# HIVE_BOARD_CHANNEL_HW.net
KiCad netlist of a schematic drawn in Altium Designer
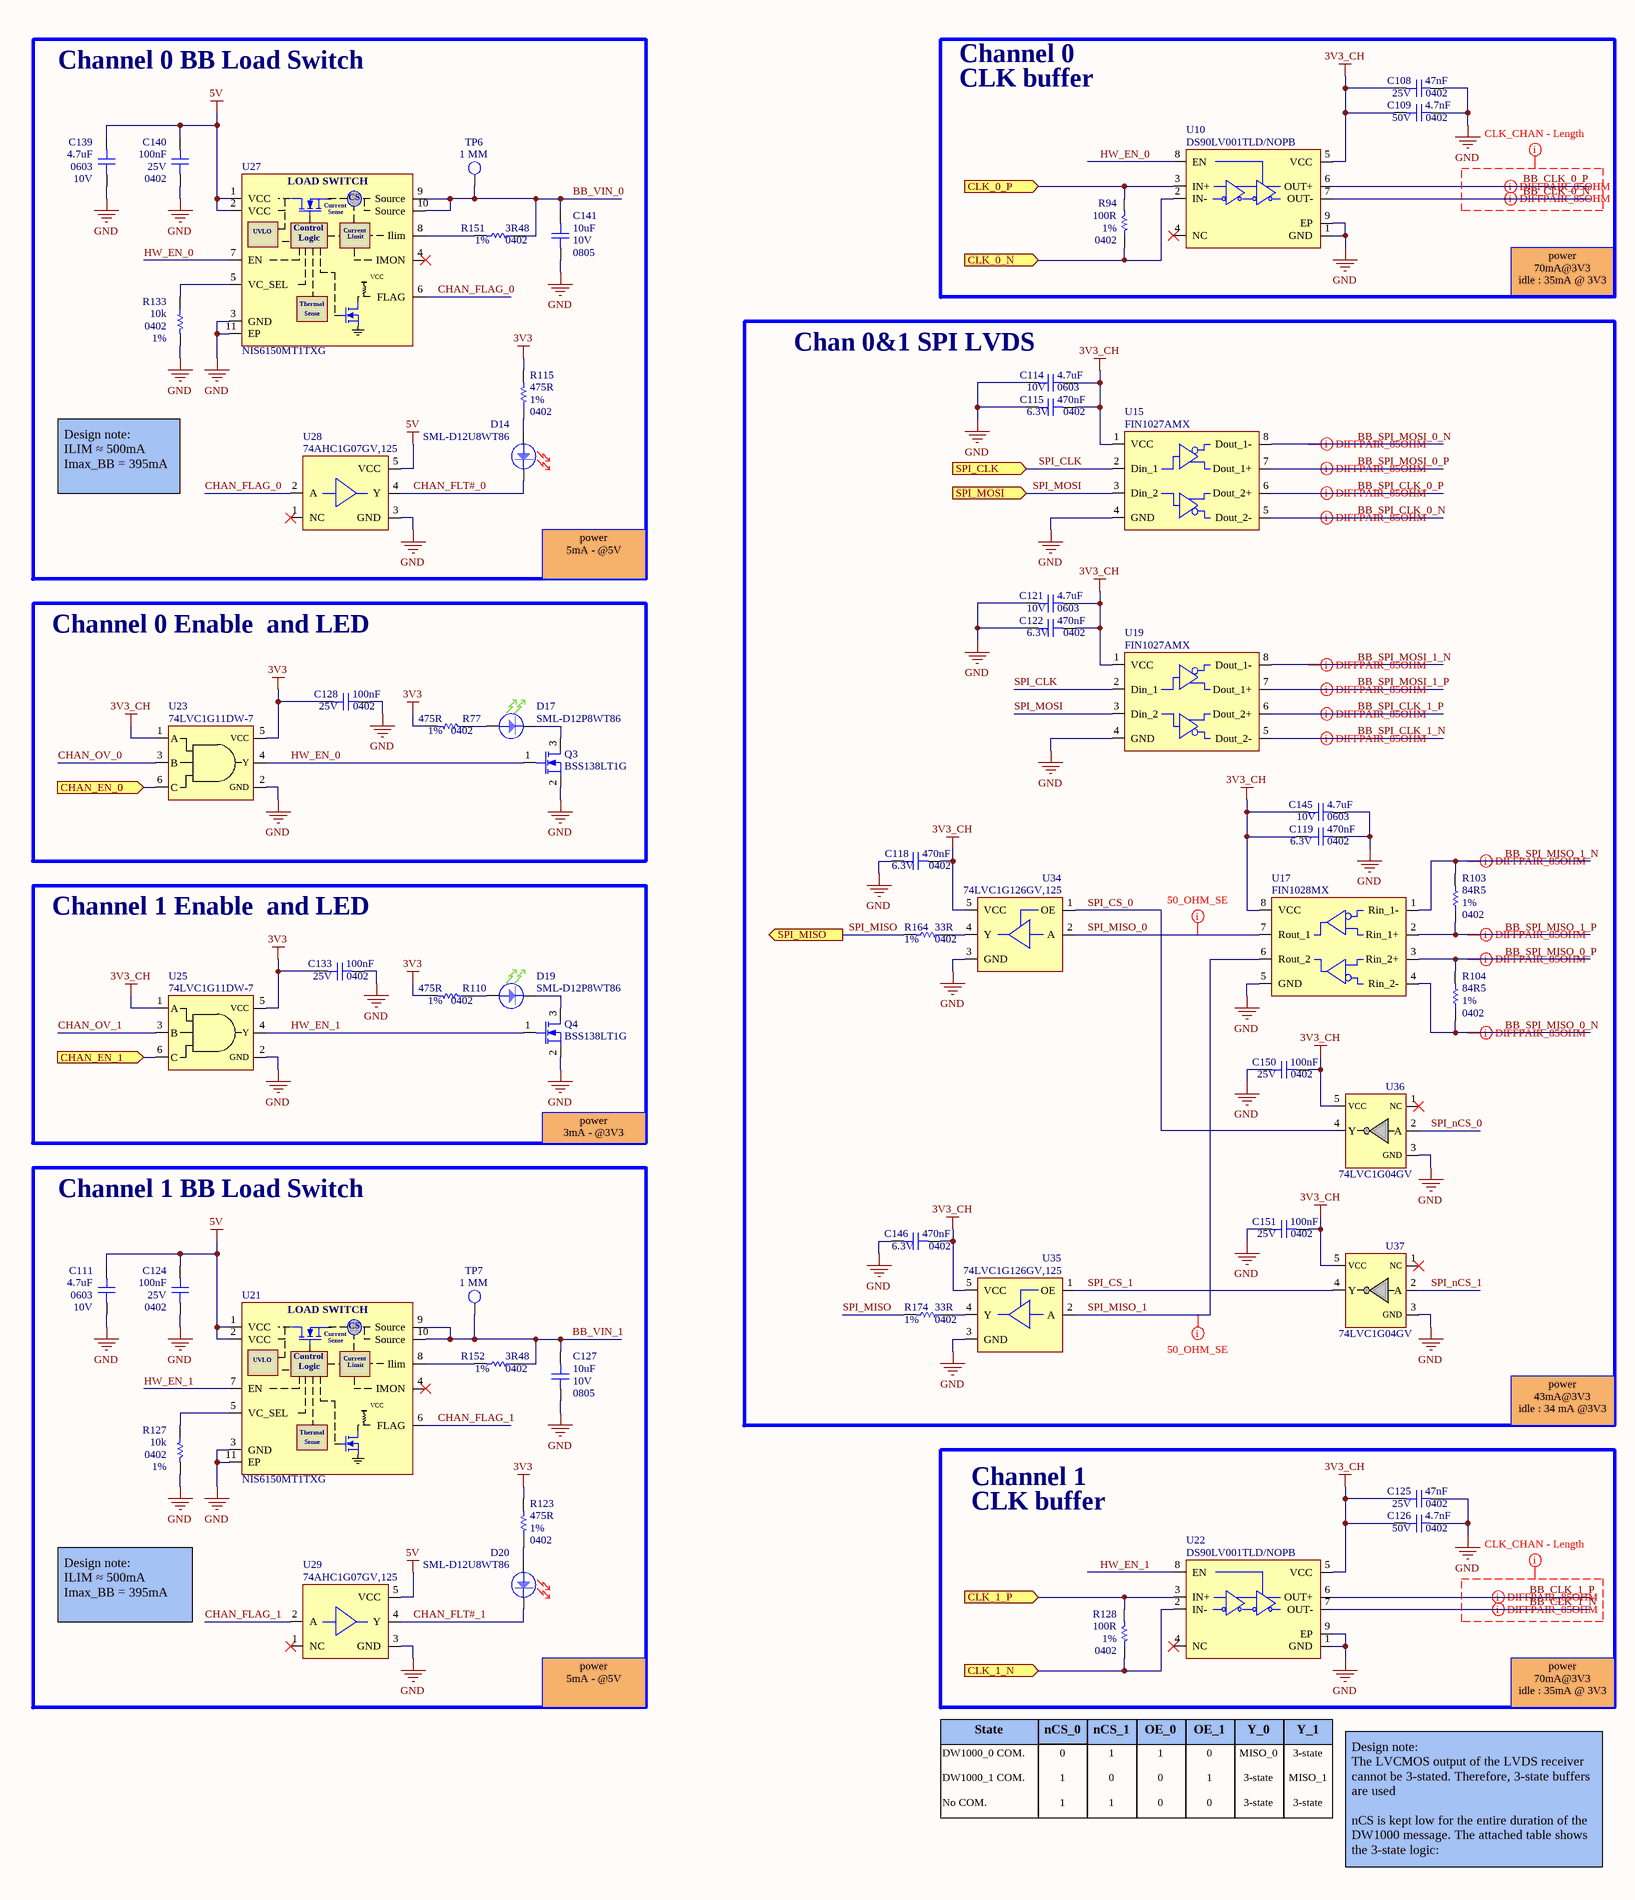
[diagram p0: HIVE_BOARD_CHANNEL_HW.SchDoc, left]
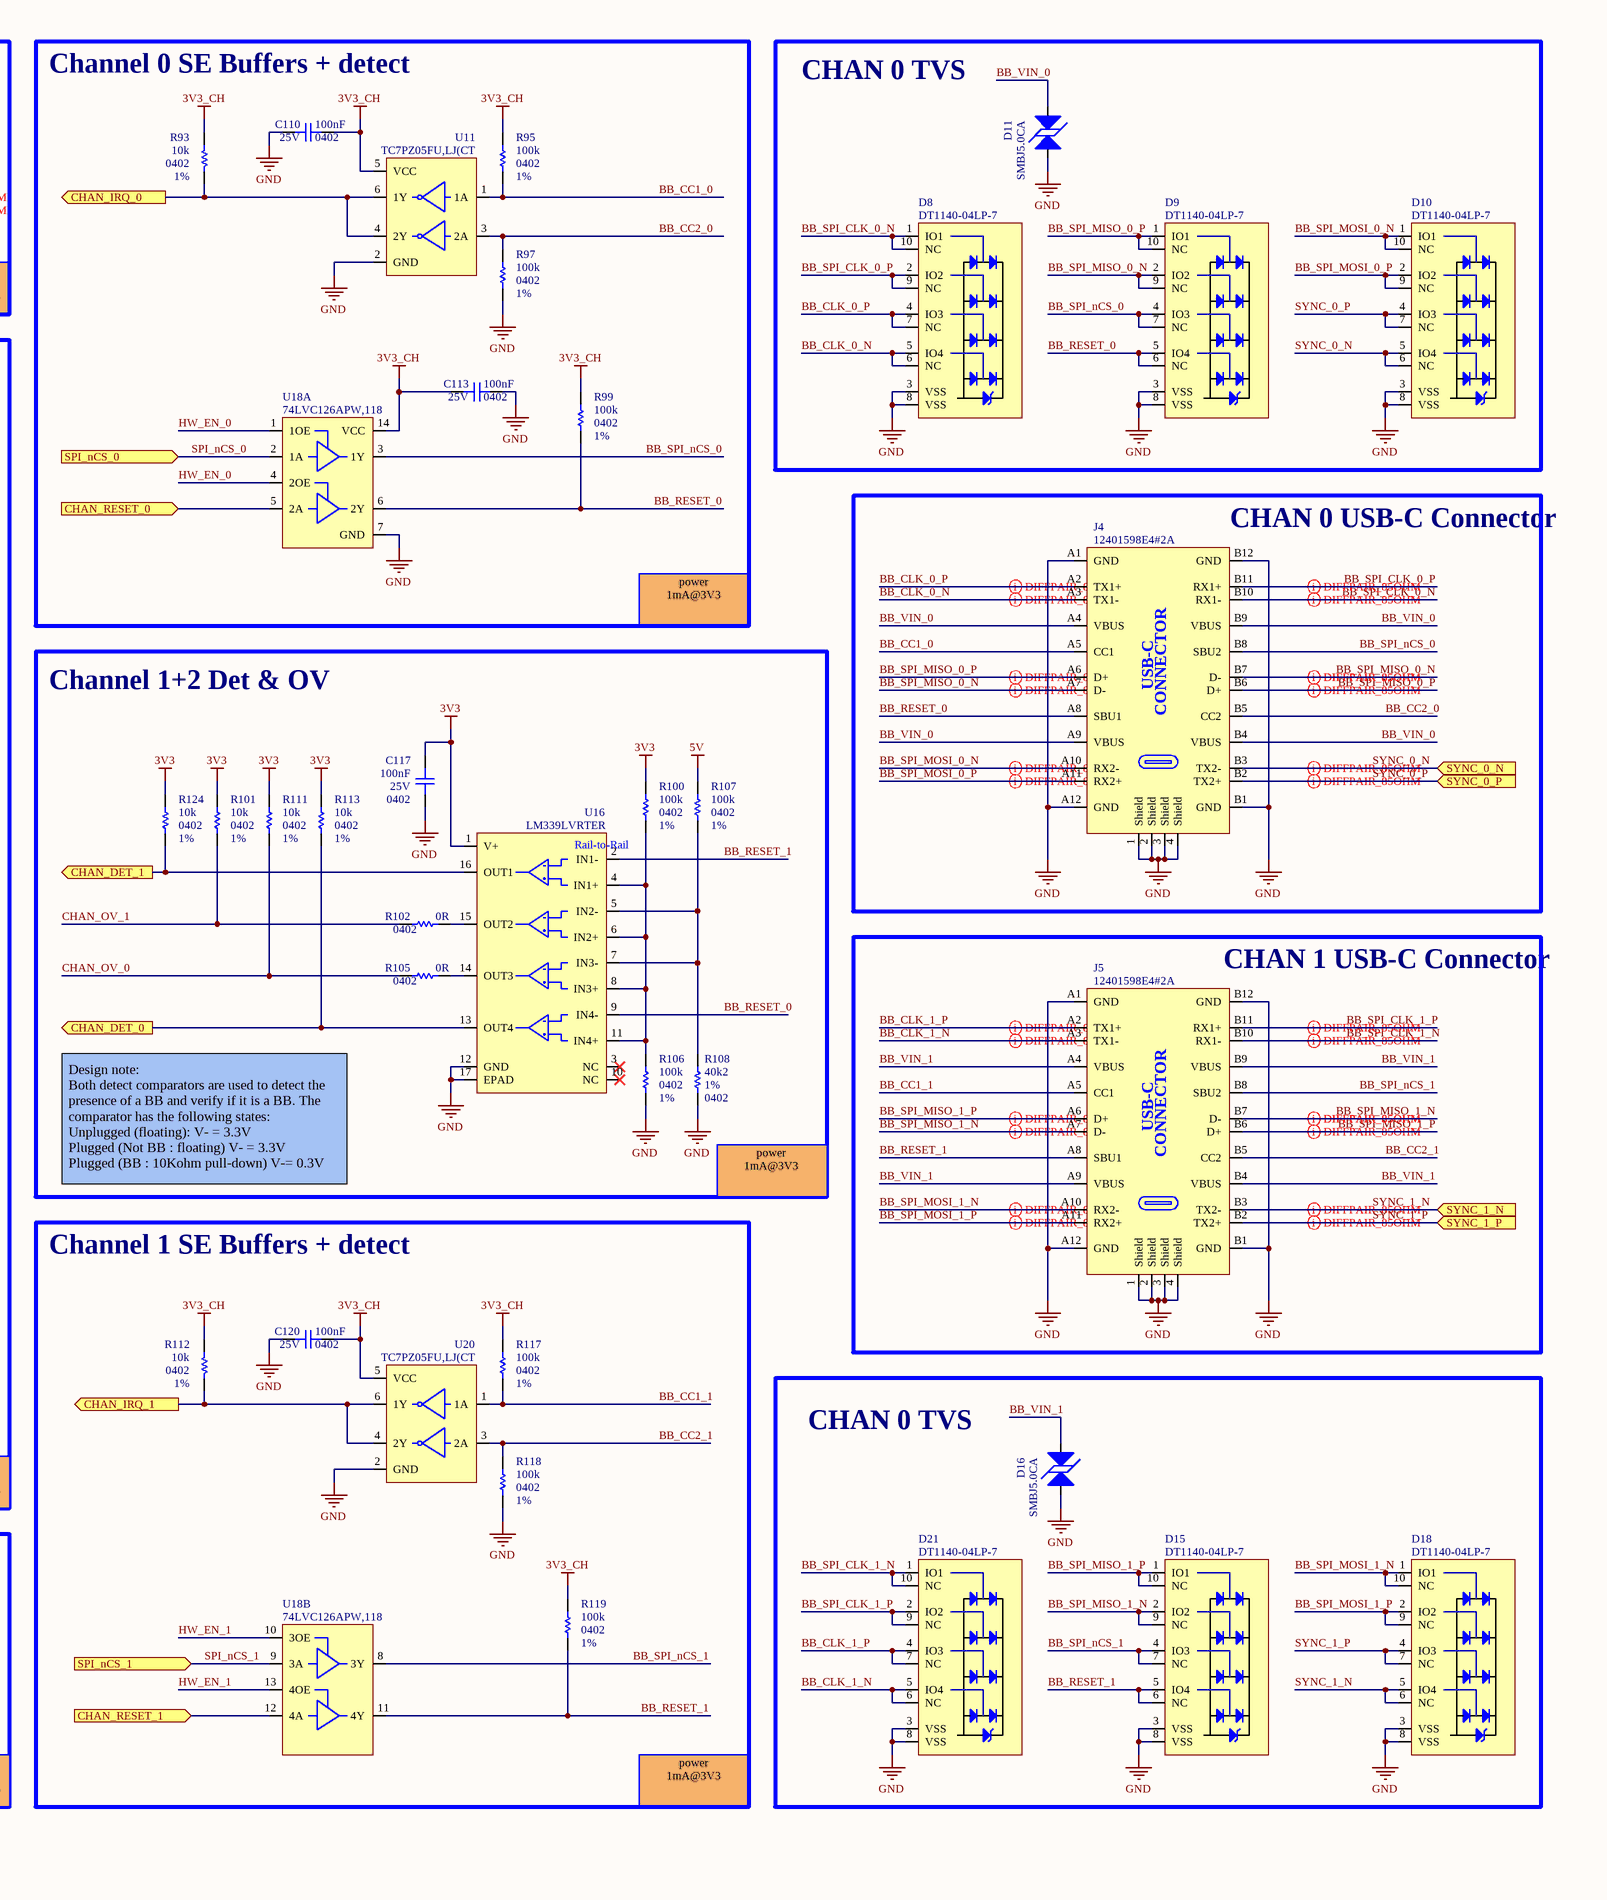
[diagram p1: HIVE_BOARD_CHANNEL_HW.SchDoc, right]

(export (version "E")
  (design (tool "Eeschema 10.0.6"))
  (components
    (comp (ref "C108")
      (value "47nF")
      (footprint "CAP_CER_0402")
      (description "CAP - CER 47nF 25V X7R - 0402")
      (fields
        (field (name "TOLERANCE") "10%")
        (field (name "PACKAGE") "0402")
        (field (name "VOLTAGE RATING") "25V")
        (field (name "Comment") "GRM155R71E473KA88J")
        (field (name "CREATEDBY/DATE") "P. Marcoux 2020-02-05")
        (field (name "VERIFIEDBY") "C.Paulin - 22/04/2020")
      )
      (libsource (lib "GRAMS_MASTER_LIB") (part "CAP_CER_GRM155R71E473KA88J"))
    )
    (comp (ref "C109")
      (value "4.7nF")
      (footprint "CAP_CER_0402")
      (description "CAP - CER 4700PF 50V X7R 0402")
      (fields
        (field (name "TOLERANCE") "±10%")
        (field (name "PACKAGE") "0402")
        (field (name "VOLTAGE RATING") "50V")
        (field (name "Comment") "CL05B472KB5VPNC")
        (field (name "CREATEDBY/DATE") "Philippe Arsenault/ 2021-03-26")
      )
      (libsource (lib "SWARMUS_LIB") (part "CAP_CER_CL05B472KB5VPNC"))
    )
    (comp (ref "C110")
      (value "100nF")
      (footprint "CAP_CER_0402")
      (description "CAP - CER 0.1µF 10% 25V X7R - 0402")
      (fields
        (field (name "TOLERANCE") "10%")
        (field (name "PACKAGE") "0402")
        (field (name "VOLTAGE RATING") "25V")
        (field (name "Comment") "CGA2B3X7R1E104K050BB")
        (field (name "CREATEDBY/DATE") "Nicolas Roy 2018-11-07")
        (field (name "VERIFIEDBY") "Nicolas V. (2019-01-22)")
      )
      (libsource (lib "GRAMS_MASTER_LIB") (part "CAP_CER_CGA2B3X7R1E104K050BB"))
    )
    (comp (ref "C111")
      (value "4.7uF")
      (footprint "CAP_CER_0603")
      (description "4.7µF ±10% 10V Ceramic Capacitor X5R 0603")
      (fields
        (field (name "TOLERANCE") "10%")
        (field (name "PACKAGE") "0603")
        (field (name "VOLTAGE RATING") "10V")
        (field (name "Comment") "CL10A475KP8NNNC")
        (field (name "CREATEDBY/DATE") "Hubert Dube - 25/02/2021")
        (field (name "VERIFIEDBY") "Philippe Arsenault/2021-03-14")
      )
      (libsource (lib "SWARMUS_LIB") (part "CAP_CER_CL10A475KP8NNNC"))
    )
    (comp (ref "C113")
      (value "100nF")
      (footprint "CAP_CER_0402")
      (description "CAP - CER 0.1µF 10% 25V X7R - 0402")
      (fields
        (field (name "TOLERANCE") "10%")
        (field (name "PACKAGE") "0402")
        (field (name "VOLTAGE RATING") "25V")
        (field (name "Comment") "CGA2B3X7R1E104K050BB")
        (field (name "CREATEDBY/DATE") "Nicolas Roy 2018-11-07")
        (field (name "VERIFIEDBY") "Nicolas V. (2019-01-22)")
      )
      (libsource (lib "GRAMS_MASTER_LIB") (part "CAP_CER_CGA2B3X7R1E104K050BB"))
    )
    (comp (ref "C114")
      (value "4.7uF")
      (footprint "CAP_CER_0603")
      (description "4.7µF ±10% 10V Ceramic Capacitor X5R 0603")
      (fields
        (field (name "TOLERANCE") "10%")
        (field (name "PACKAGE") "0603")
        (field (name "VOLTAGE RATING") "10V")
        (field (name "Comment") "CL10A475KP8NNNC")
        (field (name "CREATEDBY/DATE") "Hubert Dube - 25/02/2021")
        (field (name "VERIFIEDBY") "Philippe Arsenault/2021-03-14")
      )
      (libsource (lib "SWARMUS_LIB") (part "CAP_CER_CL10A475KP8NNNC"))
    )
    (comp (ref "C115")
      (value "470nF")
      (footprint "CAP_CER_0402")
      (description "CAP - CER 470nF 6.3V X7R - 0402")
      (fields
        (field (name "TOLERANCE") "10%")
        (field (name "PACKAGE") "0402")
        (field (name "VOLTAGE RATING") "6.3V")
        (field (name "Comment") "JMK105B7474KVHF")
        (field (name "CREATEDBY/DATE") "Nicolas (2019-06-21)")
        (field (name "VERIFIEDBY") "Nicolas V. (2019-06-21)")
      )
      (libsource (lib "GRAMS_MASTER_LIB") (part "CAP_CER_JMK105B7474KVHF"))
    )
    (comp (ref "C117")
      (value "100nF")
      (footprint "CAP_CER_0402")
      (description "CAP - CER 0.1µF 10% 25V X7R - 0402")
      (fields
        (field (name "TOLERANCE") "10%")
        (field (name "PACKAGE") "0402")
        (field (name "VOLTAGE RATING") "25V")
        (field (name "Comment") "CGA2B3X7R1E104K050BB")
        (field (name "CREATEDBY/DATE") "Nicolas Roy 2018-11-07")
        (field (name "VERIFIEDBY") "Nicolas V. (2019-01-22)")
      )
      (libsource (lib "GRAMS_MASTER_LIB") (part "CAP_CER_CGA2B3X7R1E104K050BB"))
    )
    (comp (ref "C118")
      (value "470nF")
      (footprint "CAP_CER_0402")
      (description "CAP - CER 470nF 6.3V X7R - 0402")
      (fields
        (field (name "TOLERANCE") "10%")
        (field (name "PACKAGE") "0402")
        (field (name "VOLTAGE RATING") "6.3V")
        (field (name "Comment") "JMK105B7474KVHF")
        (field (name "CREATEDBY/DATE") "Nicolas (2019-06-21)")
        (field (name "VERIFIEDBY") "Nicolas V. (2019-06-21)")
      )
      (libsource (lib "GRAMS_MASTER_LIB") (part "CAP_CER_JMK105B7474KVHF"))
    )
    (comp (ref "C119")
      (value "470nF")
      (footprint "CAP_CER_0402")
      (description "CAP - CER 470nF 6.3V X7R - 0402")
      (fields
        (field (name "TOLERANCE") "10%")
        (field (name "PACKAGE") "0402")
        (field (name "VOLTAGE RATING") "6.3V")
        (field (name "Comment") "JMK105B7474KVHF")
        (field (name "CREATEDBY/DATE") "Nicolas (2019-06-21)")
        (field (name "VERIFIEDBY") "Nicolas V. (2019-06-21)")
      )
      (libsource (lib "GRAMS_MASTER_LIB") (part "CAP_CER_JMK105B7474KVHF"))
    )
    (comp (ref "C120")
      (value "100nF")
      (footprint "CAP_CER_0402")
      (description "CAP - CER 0.1µF 10% 25V X7R - 0402")
      (fields
        (field (name "TOLERANCE") "10%")
        (field (name "PACKAGE") "0402")
        (field (name "VOLTAGE RATING") "25V")
        (field (name "Comment") "CGA2B3X7R1E104K050BB")
        (field (name "CREATEDBY/DATE") "Nicolas Roy 2018-11-07")
        (field (name "VERIFIEDBY") "Nicolas V. (2019-01-22)")
      )
      (libsource (lib "GRAMS_MASTER_LIB") (part "CAP_CER_CGA2B3X7R1E104K050BB"))
    )
    (comp (ref "C121")
      (value "4.7uF")
      (footprint "CAP_CER_0603")
      (description "4.7µF ±10% 10V Ceramic Capacitor X5R 0603")
      (fields
        (field (name "TOLERANCE") "10%")
        (field (name "PACKAGE") "0603")
        (field (name "VOLTAGE RATING") "10V")
        (field (name "Comment") "CL10A475KP8NNNC")
        (field (name "CREATEDBY/DATE") "Hubert Dube - 25/02/2021")
        (field (name "VERIFIEDBY") "Philippe Arsenault/2021-03-14")
      )
      (libsource (lib "SWARMUS_LIB") (part "CAP_CER_CL10A475KP8NNNC"))
    )
    (comp (ref "C122")
      (value "470nF")
      (footprint "CAP_CER_0402")
      (description "CAP - CER 470nF 6.3V X7R - 0402")
      (fields
        (field (name "TOLERANCE") "10%")
        (field (name "PACKAGE") "0402")
        (field (name "VOLTAGE RATING") "6.3V")
        (field (name "Comment") "JMK105B7474KVHF")
        (field (name "CREATEDBY/DATE") "Nicolas (2019-06-21)")
        (field (name "VERIFIEDBY") "Nicolas V. (2019-06-21)")
      )
      (libsource (lib "GRAMS_MASTER_LIB") (part "CAP_CER_JMK105B7474KVHF"))
    )
    (comp (ref "C124")
      (value "100nF")
      (footprint "CAP_CER_0402")
      (description "CAP - CER 0.1µF 10% 25V X7R - 0402")
      (fields
        (field (name "TOLERANCE") "10%")
        (field (name "PACKAGE") "0402")
        (field (name "VOLTAGE RATING") "25V")
        (field (name "Comment") "CGA2B3X7R1E104K050BB")
        (field (name "CREATEDBY/DATE") "Nicolas Roy 2018-11-07")
        (field (name "VERIFIEDBY") "Nicolas V. (2019-01-22)")
      )
      (libsource (lib "GRAMS_MASTER_LIB") (part "CAP_CER_CGA2B3X7R1E104K050BB"))
    )
    (comp (ref "C125")
      (value "47nF")
      (footprint "CAP_CER_0402")
      (description "CAP - CER 47nF 25V X7R - 0402")
      (fields
        (field (name "TOLERANCE") "10%")
        (field (name "PACKAGE") "0402")
        (field (name "VOLTAGE RATING") "25V")
        (field (name "Comment") "GRM155R71E473KA88J")
        (field (name "CREATEDBY/DATE") "P. Marcoux 2020-02-05")
        (field (name "VERIFIEDBY") "C.Paulin - 22/04/2020")
      )
      (libsource (lib "GRAMS_MASTER_LIB") (part "CAP_CER_GRM155R71E473KA88J"))
    )
    (comp (ref "C126")
      (value "4.7nF")
      (footprint "CAP_CER_0402")
      (description "CAP - CER 4700PF 50V X7R 0402")
      (fields
        (field (name "TOLERANCE") "±10%")
        (field (name "PACKAGE") "0402")
        (field (name "VOLTAGE RATING") "50V")
        (field (name "Comment") "CL05B472KB5VPNC")
        (field (name "CREATEDBY/DATE") "Philippe Arsenault/ 2021-03-26")
      )
      (libsource (lib "SWARMUS_LIB") (part "CAP_CER_CL05B472KB5VPNC"))
    )
    (comp (ref "C127")
      (value "10uF")
      (footprint "CAP_CER_0805")
      (description "CAP - CER 10UF 10% 10V X5R - 0805")
      (fields
        (field (name "TOLERANCE") "10%")
        (field (name "PACKAGE") "0805")
        (field (name "VOLTAGE RATING") "10V")
        (field (name "Comment") "LMK212BJ106KG-T")
        (field (name "CREATEDBY/DATE") "Caroline Paulin / 25 juillet 2018")
        (field (name "VERIFIEDBY") "Nicolas V. (2019-01-22)")
      )
      (libsource (lib "GRAMS_MASTER_LIB") (part "CAP_CER_LMK212BJ106KG-T"))
    )
    (comp (ref "C128")
      (value "100nF")
      (footprint "CAP_CER_0402")
      (description "CAP - CER 0.1µF 10% 25V X7R - 0402")
      (fields
        (field (name "TOLERANCE") "10%")
        (field (name "PACKAGE") "0402")
        (field (name "VOLTAGE RATING") "25V")
        (field (name "Comment") "CGA2B3X7R1E104K050BB")
        (field (name "CREATEDBY/DATE") "Nicolas Roy 2018-11-07")
        (field (name "VERIFIEDBY") "Nicolas V. (2019-01-22)")
      )
      (libsource (lib "GRAMS_MASTER_LIB") (part "CAP_CER_CGA2B3X7R1E104K050BB"))
    )
    (comp (ref "C133")
      (value "100nF")
      (footprint "CAP_CER_0402")
      (description "CAP - CER 0.1µF 10% 25V X7R - 0402")
      (fields
        (field (name "TOLERANCE") "10%")
        (field (name "PACKAGE") "0402")
        (field (name "VOLTAGE RATING") "25V")
        (field (name "Comment") "CGA2B3X7R1E104K050BB")
        (field (name "CREATEDBY/DATE") "Nicolas Roy 2018-11-07")
        (field (name "VERIFIEDBY") "Nicolas V. (2019-01-22)")
      )
      (libsource (lib "GRAMS_MASTER_LIB") (part "CAP_CER_CGA2B3X7R1E104K050BB"))
    )
    (comp (ref "C139")
      (value "4.7uF")
      (footprint "CAP_CER_0603")
      (description "4.7µF ±10% 10V Ceramic Capacitor X5R 0603")
      (fields
        (field (name "TOLERANCE") "10%")
        (field (name "PACKAGE") "0603")
        (field (name "VOLTAGE RATING") "10V")
        (field (name "Comment") "CL10A475KP8NNNC")
        (field (name "CREATEDBY/DATE") "Hubert Dube - 25/02/2021")
        (field (name "VERIFIEDBY") "Philippe Arsenault/2021-03-14")
      )
      (libsource (lib "SWARMUS_LIB") (part "CAP_CER_CL10A475KP8NNNC"))
    )
    (comp (ref "C140")
      (value "100nF")
      (footprint "CAP_CER_0402")
      (description "CAP - CER 0.1µF 10% 25V X7R - 0402")
      (fields
        (field (name "TOLERANCE") "10%")
        (field (name "PACKAGE") "0402")
        (field (name "VOLTAGE RATING") "25V")
        (field (name "Comment") "CGA2B3X7R1E104K050BB")
        (field (name "CREATEDBY/DATE") "Nicolas Roy 2018-11-07")
        (field (name "VERIFIEDBY") "Nicolas V. (2019-01-22)")
      )
      (libsource (lib "GRAMS_MASTER_LIB") (part "CAP_CER_CGA2B3X7R1E104K050BB"))
    )
    (comp (ref "C141")
      (value "10uF")
      (footprint "CAP_CER_0805")
      (description "CAP - CER 10UF 10% 10V X5R - 0805")
      (fields
        (field (name "TOLERANCE") "10%")
        (field (name "PACKAGE") "0805")
        (field (name "VOLTAGE RATING") "10V")
        (field (name "Comment") "LMK212BJ106KG-T")
        (field (name "CREATEDBY/DATE") "Caroline Paulin / 25 juillet 2018")
        (field (name "VERIFIEDBY") "Nicolas V. (2019-01-22)")
      )
      (libsource (lib "GRAMS_MASTER_LIB") (part "CAP_CER_LMK212BJ106KG-T"))
    )
    (comp (ref "C145")
      (value "4.7uF")
      (footprint "CAP_CER_0603")
      (description "4.7µF ±10% 10V Ceramic Capacitor X5R 0603")
      (fields
        (field (name "TOLERANCE") "10%")
        (field (name "PACKAGE") "0603")
        (field (name "VOLTAGE RATING") "10V")
        (field (name "Comment") "CL10A475KP8NNNC")
        (field (name "CREATEDBY/DATE") "Hubert Dube - 25/02/2021")
        (field (name "VERIFIEDBY") "Philippe Arsenault/2021-03-14")
      )
      (libsource (lib "SWARMUS_LIB") (part "CAP_CER_CL10A475KP8NNNC"))
    )
    (comp (ref "C146")
      (value "470nF")
      (footprint "CAP_CER_0402")
      (description "CAP - CER 470nF 6.3V X7R - 0402")
      (fields
        (field (name "TOLERANCE") "10%")
        (field (name "PACKAGE") "0402")
        (field (name "VOLTAGE RATING") "6.3V")
        (field (name "Comment") "JMK105B7474KVHF")
        (field (name "CREATEDBY/DATE") "Nicolas (2019-06-21)")
        (field (name "VERIFIEDBY") "Nicolas V. (2019-06-21)")
      )
      (libsource (lib "GRAMS_MASTER_LIB") (part "CAP_CER_JMK105B7474KVHF"))
    )
    (comp (ref "C150")
      (value "100nF")
      (footprint "CAP_CER_0402")
      (description "CAP - CER 0.1µF 10% 25V X7R - 0402")
      (fields
        (field (name "TOLERANCE") "10%")
        (field (name "PACKAGE") "0402")
        (field (name "VOLTAGE RATING") "25V")
        (field (name "Comment") "CGA2B3X7R1E104K050BB")
        (field (name "CREATEDBY/DATE") "Nicolas Roy 2018-11-07")
        (field (name "VERIFIEDBY") "Nicolas V. (2019-01-22)")
      )
      (libsource (lib "GRAMS_MASTER_LIB") (part "CAP_CER_CGA2B3X7R1E104K050BB"))
    )
    (comp (ref "C151")
      (value "100nF")
      (footprint "CAP_CER_0402")
      (description "CAP - CER 0.1µF 10% 25V X7R - 0402")
      (fields
        (field (name "TOLERANCE") "10%")
        (field (name "PACKAGE") "0402")
        (field (name "VOLTAGE RATING") "25V")
        (field (name "Comment") "CGA2B3X7R1E104K050BB")
        (field (name "CREATEDBY/DATE") "Nicolas Roy 2018-11-07")
        (field (name "VERIFIEDBY") "Nicolas V. (2019-01-22)")
      )
      (libsource (lib "GRAMS_MASTER_LIB") (part "CAP_CER_CGA2B3X7R1E104K050BB"))
    )
    (comp (ref "D8")
      (value "DT1140-04LP-7")
      (footprint "TVS_DATA_DT1140-04LP-7")
      (description "TVS - DIODE 5.5V 10V - 10-UFDFN")
      (fields
        (field (name "CREATEDBY/DATE") "Joël Lemay 2019-11-20")
        (field (name "VERIFIEDBY") "C.Paulin - 21/11/2019")
      )
      (libsource (lib "GRAMS_MASTER_LIB") (part "TVS_DATA_DT1140-04LP-7"))
    )
    (comp (ref "D9")
      (value "DT1140-04LP-7")
      (footprint "TVS_DATA_DT1140-04LP-7")
      (description "TVS - DIODE 5.5V 10V - 10-UFDFN")
      (fields
        (field (name "CREATEDBY/DATE") "Joël Lemay 2019-11-20")
        (field (name "VERIFIEDBY") "C.Paulin - 21/11/2019")
      )
      (libsource (lib "GRAMS_MASTER_LIB") (part "TVS_DATA_DT1140-04LP-7"))
    )
    (comp (ref "D10")
      (value "DT1140-04LP-7")
      (footprint "TVS_DATA_DT1140-04LP-7")
      (description "TVS - DIODE 5.5V 10V - 10-UFDFN")
      (fields
        (field (name "CREATEDBY/DATE") "Joël Lemay 2019-11-20")
        (field (name "VERIFIEDBY") "C.Paulin - 21/11/2019")
      )
      (libsource (lib "GRAMS_MASTER_LIB") (part "TVS_DATA_DT1140-04LP-7"))
    )
    (comp (ref "D11")
      (value "SMBJ5.0CA")
      (footprint "TVS_PWR_SMBJ5.0CA")
      (description "TVS - BIDIR 5V 9.2V 600W - DO214AA")
      (fields
        (field (name "CREATEDBY/DATE") "Jonathan Bouchard - 2019-03-22")
        (field (name "VERIFIEDBY") "Nicolas V. (2019-05-06)")
      )
      (libsource (lib "GRAMS_MASTER_LIB") (part "TVS_PWR_SMBJ5.0CA"))
    )
    (comp (ref "D14")
      (value "SML-D12U8WT86")
      (footprint "LED_SML-D12U8WT86")
      (description "LED - RED DIFFUSED 0603 SMD - 0603")
      (fields
        (field (name "CREATEDBY/DATE") "Olivier Bernard / 01/02/2018")
        (field (name "VERIFIEDBY") "Caroline Paulin / 6 juillet 2018")
      )
      (libsource (lib "GRAMS_MASTER_LIB") (part "LED_SML-D12U8WT86"))
    )
    (comp (ref "D15")
      (value "DT1140-04LP-7")
      (footprint "TVS_DATA_DT1140-04LP-7")
      (description "TVS - DIODE 5.5V 10V - 10-UFDFN")
      (fields
        (field (name "CREATEDBY/DATE") "Joël Lemay 2019-11-20")
        (field (name "VERIFIEDBY") "C.Paulin - 21/11/2019")
      )
      (libsource (lib "GRAMS_MASTER_LIB") (part "TVS_DATA_DT1140-04LP-7"))
    )
    (comp (ref "D16")
      (value "SMBJ5.0CA")
      (footprint "TVS_PWR_SMBJ5.0CA")
      (description "TVS - BIDIR 5V 9.2V 600W - DO214AA")
      (fields
        (field (name "CREATEDBY/DATE") "Jonathan Bouchard - 2019-03-22")
        (field (name "VERIFIEDBY") "Nicolas V. (2019-05-06)")
      )
      (libsource (lib "GRAMS_MASTER_LIB") (part "TVS_PWR_SMBJ5.0CA"))
    )
    (comp (ref "D17")
      (value "SML-D12P8WT86")
      (footprint "LED_SML-D12P8WT86")
      (description "LED - GREEN DIFFUSED 0603 SMD - 0603")
      (fields
        (field (name "CREATEDBY/DATE") "Keven Deslandes - 2018/11/21")
        (field (name "VERIFIEDBY") "Caroline Paulin - 13 février 2019")
      )
      (libsource (lib "GRAMS_MASTER_LIB") (part "LED_SML-D12P8WT86"))
    )
    (comp (ref "D18")
      (value "DT1140-04LP-7")
      (footprint "TVS_DATA_DT1140-04LP-7")
      (description "TVS - DIODE 5.5V 10V - 10-UFDFN")
      (fields
        (field (name "CREATEDBY/DATE") "Joël Lemay 2019-11-20")
        (field (name "VERIFIEDBY") "C.Paulin - 21/11/2019")
      )
      (libsource (lib "GRAMS_MASTER_LIB") (part "TVS_DATA_DT1140-04LP-7"))
    )
    (comp (ref "D19")
      (value "SML-D12P8WT86")
      (footprint "LED_SML-D12P8WT86")
      (description "LED - GREEN DIFFUSED 0603 SMD - 0603")
      (fields
        (field (name "CREATEDBY/DATE") "Keven Deslandes - 2018/11/21")
        (field (name "VERIFIEDBY") "Caroline Paulin - 13 février 2019")
      )
      (libsource (lib "GRAMS_MASTER_LIB") (part "LED_SML-D12P8WT86"))
    )
    (comp (ref "D20")
      (value "SML-D12U8WT86")
      (footprint "LED_SML-D12U8WT86")
      (description "LED - RED DIFFUSED 0603 SMD - 0603")
      (fields
        (field (name "CREATEDBY/DATE") "Olivier Bernard / 01/02/2018")
        (field (name "VERIFIEDBY") "Caroline Paulin / 6 juillet 2018")
      )
      (libsource (lib "GRAMS_MASTER_LIB") (part "LED_SML-D12U8WT86"))
    )
    (comp (ref "D21")
      (value "DT1140-04LP-7")
      (footprint "TVS_DATA_DT1140-04LP-7")
      (description "TVS - DIODE 5.5V 10V - 10-UFDFN")
      (fields
        (field (name "CREATEDBY/DATE") "Joël Lemay 2019-11-20")
        (field (name "VERIFIEDBY") "C.Paulin - 21/11/2019")
      )
      (libsource (lib "GRAMS_MASTER_LIB") (part "TVS_DATA_DT1140-04LP-7"))
    )
    (comp (ref "J4")
      (value "12401598E4#2A")
      (footprint "CON_USB_3.2_TypeC_12401598E4#2A")
      (description "CON_USB - USB 3.2 Gen 2 (USB 3.1 Gen 2, Superspeed + (USB 3.1)) 24 pos Receptacle - R/A")
      (fields
        (field (name "CREATEDBY/DATE") "Louis-Daniel Gaulin / 07-04-2021")
        (field (name "VERIFIEDBY") "Philippe Arsenault/2021-04-08")
      )
      (libsource (lib "SWARMUS_LIB") (part "CON_USB_3.2_TypeC_12401598E4#2A"))
    )
    (comp (ref "J5")
      (value "12401598E4#2A")
      (footprint "CON_USB_3.2_TypeC_12401598E4#2A")
      (description "CON_USB - USB 3.2 Gen 2 (USB 3.1 Gen 2, Superspeed + (USB 3.1)) 24 pos Receptacle - R/A")
      (fields
        (field (name "CREATEDBY/DATE") "Louis-Daniel Gaulin / 07-04-2021")
        (field (name "VERIFIEDBY") "Philippe Arsenault/2021-04-08")
      )
      (libsource (lib "SWARMUS_LIB") (part "CON_USB_3.2_TypeC_12401598E4#2A"))
    )
    (comp (ref "Q3")
      (value "BSS138LT1G")
      (footprint "TRX_NMOS_BSS138LT1G")
      (description "TRX - NMOS - 50V 200MA - SOT−23-3")
      (fields
        (field (name "CREATEDBY/DATE") "Joel Lemay 2018-06-15")
        (field (name "VERIFIEDBY") "Caroline Paulin - 6 sept 2018")
      )
      (libsource (lib "GRAMS_MASTER_LIB") (part "TRX_NMOS_BSS138LT1G"))
    )
    (comp (ref "Q4")
      (value "BSS138LT1G")
      (footprint "TRX_NMOS_BSS138LT1G")
      (description "TRX - NMOS - 50V 200MA - SOT−23-3")
      (fields
        (field (name "CREATEDBY/DATE") "Joel Lemay 2018-06-15")
        (field (name "VERIFIEDBY") "Caroline Paulin - 6 sept 2018")
      )
      (libsource (lib "GRAMS_MASTER_LIB") (part "TRX_NMOS_BSS138LT1G"))
    )
    (comp (ref "R77")
      (value "475R")
      (footprint "RES_0402")
      (description "RES - 475R 1% 1/10W- 0402")
      (fields
        (field (name "TOLERANCE") "1%")
        (field (name "PACKAGE") "0402")
        (field (name "Comment") "ERJ-2RKF4750X")
        (field (name "CREATEDBY/DATE") "Keven Deslandes 2018-10-17")
        (field (name "VERIFIEDBY") "Carolilne Paulin - 18/12/2018")
      )
      (libsource (lib "GRAMS_MASTER_LIB") (part "RES_ERJ-2RKF4750X"))
    )
    (comp (ref "R93")
      (value "10k")
      (footprint "RES_0402")
      (description "RES - 10K OHMS 1% 1/16W - 0402")
      (fields
        (field (name "TOLERANCE") "1%")
        (field (name "PACKAGE") "0402")
        (field (name "Comment") "RC0402FR-0710KL")
        (field (name "CREATEDBY/DATE") "Nicolas V. (2018-11-20)")
        (field (name "VERIFIEDBY") "Nicolas V. (2018-11-20)")
      )
      (libsource (lib "GRAMS_MASTER_LIB") (part "RES_RC0402FR-0710KL"))
    )
    (comp (ref "R94")
      (value "100R")
      (footprint "RES_0402")
      (description "RES - 100R OHM 1% 1/16W - 0402")
      (fields
        (field (name "TOLERANCE") "1%")
        (field (name "PACKAGE") "0402")
        (field (name "Comment") "RC0402FR-07100RP")
        (field (name "CREATEDBY/DATE") "Jonathan Bouchard 2018-07-05")
        (field (name "VERIFIEDBY") "Arnaud Samson 16-07-18")
      )
      (libsource (lib "GRAMS_MASTER_LIB") (part "RES_RC0402FR-07100RP"))
    )
    (comp (ref "R95")
      (value "100k")
      (footprint "RES_0402")
      (description "RES - 100K 1% 1/16W - 0402")
      (fields
        (field (name "TOLERANCE") "1%")
        (field (name "PACKAGE") "0402")
        (field (name "Comment") "RC0402FR-07100KL")
        (field (name "CREATEDBY/DATE") "Keven Deslandes 2018-10-19")
        (field (name "VERIFIEDBY") "Caroline Paulin - 18/12/2018")
      )
      (libsource (lib "GRAMS_MASTER_LIB") (part "RES_RC0402FR-07100KL"))
    )
    (comp (ref "R97")
      (value "100k")
      (footprint "RES_0402")
      (description "RES - 100K 1% 1/16W - 0402")
      (fields
        (field (name "TOLERANCE") "1%")
        (field (name "PACKAGE") "0402")
        (field (name "Comment") "RC0402FR-07100KL")
        (field (name "CREATEDBY/DATE") "Keven Deslandes 2018-10-19")
        (field (name "VERIFIEDBY") "Caroline Paulin - 18/12/2018")
      )
      (libsource (lib "GRAMS_MASTER_LIB") (part "RES_RC0402FR-07100KL"))
    )
    (comp (ref "R99")
      (value "100k")
      (footprint "RES_0402")
      (description "RES - 100K 1% 1/16W - 0402")
      (fields
        (field (name "TOLERANCE") "1%")
        (field (name "PACKAGE") "0402")
        (field (name "Comment") "RC0402FR-07100KL")
        (field (name "CREATEDBY/DATE") "Keven Deslandes 2018-10-19")
        (field (name "VERIFIEDBY") "Caroline Paulin - 18/12/2018")
      )
      (libsource (lib "GRAMS_MASTER_LIB") (part "RES_RC0402FR-07100KL"))
    )
    (comp (ref "R100")
      (value "100k")
      (footprint "RES_0402")
      (description "RES - 100K 1% 1/16W - 0402")
      (fields
        (field (name "TOLERANCE") "1%")
        (field (name "PACKAGE") "0402")
        (field (name "Comment") "RC0402FR-07100KL")
        (field (name "CREATEDBY/DATE") "Keven Deslandes 2018-10-19")
        (field (name "VERIFIEDBY") "Caroline Paulin - 18/12/2018")
      )
      (libsource (lib "GRAMS_MASTER_LIB") (part "RES_RC0402FR-07100KL"))
    )
    (comp (ref "R101")
      (value "10k")
      (footprint "RES_0402")
      (description "RES - 10K OHMS 1% 1/16W - 0402")
      (fields
        (field (name "TOLERANCE") "1%")
        (field (name "PACKAGE") "0402")
        (field (name "Comment") "RC0402FR-0710KL")
        (field (name "CREATEDBY/DATE") "Nicolas V. (2018-11-20)")
        (field (name "VERIFIEDBY") "Nicolas V. (2018-11-20)")
      )
      (libsource (lib "GRAMS_MASTER_LIB") (part "RES_RC0402FR-0710KL"))
    )
    (comp (ref "R102")
      (value "0R")
      (footprint "RES_0402")
      (description "RES - 0R 1/16W 1A  - 0402")
      (fields
        (field (name "PACKAGE") "0402")
        (field (name "Comment") "RC0402FR-070RL")
        (field (name "CREATEDBY/DATE") "Keven Deslandes 2018-09-12")
        (field (name "VERIFIEDBY") "Caroline Paulin - 27 fév 2019")
      )
      (libsource (lib "GRAMS_MASTER_LIB") (part "RES_RC0402FR-070RL"))
    )
    (comp (ref "R103")
      (value "84R5")
      (footprint "RES_0402")
      (description "RES - 84R5 1% 1/16W - 0402")
      (fields
        (field (name "TOLERANCE") "1%")
        (field (name "PACKAGE") "0402")
        (field (name "Comment") "RC0402FR-0784R5L")
        (field (name "CREATEDBY/DATE") "Philippe Arsenault/ 2021-03-31")
      )
      (libsource (lib "SWARMUS_LIB") (part "RES_RC0402FR-0784R5L"))
    )
    (comp (ref "R104")
      (value "84R5")
      (footprint "RES_0402")
      (description "RES - 84R5 1% 1/16W - 0402")
      (fields
        (field (name "TOLERANCE") "1%")
        (field (name "PACKAGE") "0402")
        (field (name "Comment") "RC0402FR-0784R5L")
        (field (name "CREATEDBY/DATE") "Philippe Arsenault/ 2021-03-31")
      )
      (libsource (lib "SWARMUS_LIB") (part "RES_RC0402FR-0784R5L"))
    )
    (comp (ref "R105")
      (value "0R")
      (footprint "RES_0402")
      (description "RES - 0R 1/16W 1A  - 0402")
      (fields
        (field (name "PACKAGE") "0402")
        (field (name "Comment") "RC0402FR-070RL")
        (field (name "CREATEDBY/DATE") "Keven Deslandes 2018-09-12")
        (field (name "VERIFIEDBY") "Caroline Paulin - 27 fév 2019")
      )
      (libsource (lib "GRAMS_MASTER_LIB") (part "RES_RC0402FR-070RL"))
    )
    (comp (ref "R106")
      (value "100k")
      (footprint "RES_0402")
      (description "RES - 100K 1% 1/16W - 0402")
      (fields
        (field (name "TOLERANCE") "1%")
        (field (name "PACKAGE") "0402")
        (field (name "Comment") "RC0402FR-07100KL")
        (field (name "CREATEDBY/DATE") "Keven Deslandes 2018-10-19")
        (field (name "VERIFIEDBY") "Caroline Paulin - 18/12/2018")
      )
      (libsource (lib "GRAMS_MASTER_LIB") (part "RES_RC0402FR-07100KL"))
    )
    (comp (ref "R107")
      (value "100k")
      (footprint "RES_0402")
      (description "RES - 100K 1% 1/16W - 0402")
      (fields
        (field (name "TOLERANCE") "1%")
        (field (name "PACKAGE") "0402")
        (field (name "Comment") "RC0402FR-07100KL")
        (field (name "CREATEDBY/DATE") "Keven Deslandes 2018-10-19")
        (field (name "VERIFIEDBY") "Caroline Paulin - 18/12/2018")
      )
      (libsource (lib "GRAMS_MASTER_LIB") (part "RES_RC0402FR-07100KL"))
    )
    (comp (ref "R108")
      (value "40k2")
      (footprint "RES_0402")
      (description "RES - 40.2K 1% 1/16W - 0402")
      (fields
        (field (name "TOLERANCE") "1%")
        (field (name "PACKAGE") "0402")
        (field (name "Comment") "RC0402FR-0740K2L")
        (field (name "CREATEDBY/DATE") "Raphael Bouchard - 2019-08-09")
        (field (name "VERIFIEDBY") "C.Paulin - 15/08/2019")
      )
      (libsource (lib "GRAMS_MASTER_LIB") (part "RES_RC0402FR-0740K2L"))
    )
    (comp (ref "R110")
      (value "475R")
      (footprint "RES_0402")
      (description "RES - 475R 1% 1/10W- 0402")
      (fields
        (field (name "TOLERANCE") "1%")
        (field (name "PACKAGE") "0402")
        (field (name "Comment") "ERJ-2RKF4750X")
        (field (name "CREATEDBY/DATE") "Keven Deslandes 2018-10-17")
        (field (name "VERIFIEDBY") "Carolilne Paulin - 18/12/2018")
      )
      (libsource (lib "GRAMS_MASTER_LIB") (part "RES_ERJ-2RKF4750X"))
    )
    (comp (ref "R111")
      (value "10k")
      (footprint "RES_0402")
      (description "RES - 10K OHMS 1% 1/16W - 0402")
      (fields
        (field (name "TOLERANCE") "1%")
        (field (name "PACKAGE") "0402")
        (field (name "Comment") "RC0402FR-0710KL")
        (field (name "CREATEDBY/DATE") "Nicolas V. (2018-11-20)")
        (field (name "VERIFIEDBY") "Nicolas V. (2018-11-20)")
      )
      (libsource (lib "GRAMS_MASTER_LIB") (part "RES_RC0402FR-0710KL"))
    )
    (comp (ref "R112")
      (value "10k")
      (footprint "RES_0402")
      (description "RES - 10K OHMS 1% 1/16W - 0402")
      (fields
        (field (name "TOLERANCE") "1%")
        (field (name "PACKAGE") "0402")
        (field (name "Comment") "RC0402FR-0710KL")
        (field (name "CREATEDBY/DATE") "Nicolas V. (2018-11-20)")
        (field (name "VERIFIEDBY") "Nicolas V. (2018-11-20)")
      )
      (libsource (lib "GRAMS_MASTER_LIB") (part "RES_RC0402FR-0710KL"))
    )
    (comp (ref "R113")
      (value "10k")
      (footprint "RES_0402")
      (description "RES - 10K OHMS 1% 1/16W - 0402")
      (fields
        (field (name "TOLERANCE") "1%")
        (field (name "PACKAGE") "0402")
        (field (name "Comment") "RC0402FR-0710KL")
        (field (name "CREATEDBY/DATE") "Nicolas V. (2018-11-20)")
        (field (name "VERIFIEDBY") "Nicolas V. (2018-11-20)")
      )
      (libsource (lib "GRAMS_MASTER_LIB") (part "RES_RC0402FR-0710KL"))
    )
    (comp (ref "R115")
      (value "475R")
      (footprint "RES_0402")
      (description "RES - 475R 1% 1/10W- 0402")
      (fields
        (field (name "TOLERANCE") "1%")
        (field (name "PACKAGE") "0402")
        (field (name "Comment") "ERJ-2RKF4750X")
        (field (name "CREATEDBY/DATE") "Keven Deslandes 2018-10-17")
        (field (name "VERIFIEDBY") "Carolilne Paulin - 18/12/2018")
      )
      (libsource (lib "GRAMS_MASTER_LIB") (part "RES_ERJ-2RKF4750X"))
    )
    (comp (ref "R117")
      (value "100k")
      (footprint "RES_0402")
      (description "RES - 100K 1% 1/16W - 0402")
      (fields
        (field (name "TOLERANCE") "1%")
        (field (name "PACKAGE") "0402")
        (field (name "Comment") "RC0402FR-07100KL")
        (field (name "CREATEDBY/DATE") "Keven Deslandes 2018-10-19")
        (field (name "VERIFIEDBY") "Caroline Paulin - 18/12/2018")
      )
      (libsource (lib "GRAMS_MASTER_LIB") (part "RES_RC0402FR-07100KL"))
    )
    (comp (ref "R118")
      (value "100k")
      (footprint "RES_0402")
      (description "RES - 100K 1% 1/16W - 0402")
      (fields
        (field (name "TOLERANCE") "1%")
        (field (name "PACKAGE") "0402")
        (field (name "Comment") "RC0402FR-07100KL")
        (field (name "CREATEDBY/DATE") "Keven Deslandes 2018-10-19")
        (field (name "VERIFIEDBY") "Caroline Paulin - 18/12/2018")
      )
      (libsource (lib "GRAMS_MASTER_LIB") (part "RES_RC0402FR-07100KL"))
    )
    (comp (ref "R119")
      (value "100k")
      (footprint "RES_0402")
      (description "RES - 100K 1% 1/16W - 0402")
      (fields
        (field (name "TOLERANCE") "1%")
        (field (name "PACKAGE") "0402")
        (field (name "Comment") "RC0402FR-07100KL")
        (field (name "CREATEDBY/DATE") "Keven Deslandes 2018-10-19")
        (field (name "VERIFIEDBY") "Caroline Paulin - 18/12/2018")
      )
      (libsource (lib "GRAMS_MASTER_LIB") (part "RES_RC0402FR-07100KL"))
    )
    (comp (ref "R123")
      (value "475R")
      (footprint "RES_0402")
      (description "RES - 475R 1% 1/10W- 0402")
      (fields
        (field (name "TOLERANCE") "1%")
        (field (name "PACKAGE") "0402")
        (field (name "Comment") "ERJ-2RKF4750X")
        (field (name "CREATEDBY/DATE") "Keven Deslandes 2018-10-17")
        (field (name "VERIFIEDBY") "Carolilne Paulin - 18/12/2018")
      )
      (libsource (lib "GRAMS_MASTER_LIB") (part "RES_ERJ-2RKF4750X"))
    )
    (comp (ref "R124")
      (value "10k")
      (footprint "RES_0402")
      (description "RES - 10K OHMS 1% 1/16W - 0402")
      (fields
        (field (name "TOLERANCE") "1%")
        (field (name "PACKAGE") "0402")
        (field (name "Comment") "RC0402FR-0710KL")
        (field (name "CREATEDBY/DATE") "Nicolas V. (2018-11-20)")
        (field (name "VERIFIEDBY") "Nicolas V. (2018-11-20)")
      )
      (libsource (lib "GRAMS_MASTER_LIB") (part "RES_RC0402FR-0710KL"))
    )
    (comp (ref "R127")
      (value "10k")
      (footprint "RES_0402")
      (description "RES - 10K OHMS 1% 1/16W - 0402")
      (fields
        (field (name "TOLERANCE") "1%")
        (field (name "PACKAGE") "0402")
        (field (name "Comment") "RC0402FR-0710KL")
        (field (name "CREATEDBY/DATE") "Nicolas V. (2018-11-20)")
        (field (name "VERIFIEDBY") "Nicolas V. (2018-11-20)")
      )
      (libsource (lib "GRAMS_MASTER_LIB") (part "RES_RC0402FR-0710KL"))
    )
    (comp (ref "R128")
      (value "100R")
      (footprint "RES_0402")
      (description "RES - 100R OHM 1% 1/16W - 0402")
      (fields
        (field (name "TOLERANCE") "1%")
        (field (name "PACKAGE") "0402")
        (field (name "Comment") "RC0402FR-07100RP")
        (field (name "CREATEDBY/DATE") "Jonathan Bouchard 2018-07-05")
        (field (name "VERIFIEDBY") "Arnaud Samson 16-07-18")
      )
      (libsource (lib "GRAMS_MASTER_LIB") (part "RES_RC0402FR-07100RP"))
    )
    (comp (ref "R133")
      (value "10k")
      (footprint "RES_0402")
      (description "RES - 10K OHMS 1% 1/16W - 0402")
      (fields
        (field (name "TOLERANCE") "1%")
        (field (name "PACKAGE") "0402")
        (field (name "Comment") "RC0402FR-0710KL")
        (field (name "CREATEDBY/DATE") "Nicolas V. (2018-11-20)")
        (field (name "VERIFIEDBY") "Nicolas V. (2018-11-20)")
      )
      (libsource (lib "GRAMS_MASTER_LIB") (part "RES_RC0402FR-0710KL"))
    )
    (comp (ref "R151")
      (value "3R48")
      (footprint "RES_0402")
      (description "RES - 3.48 R ±1% 1/16W -  0402")
      (fields
        (field (name "TOLERANCE") "1%")
        (field (name "PACKAGE") "0402")
        (field (name "Comment") "CRCW04023R48FKED")
        (field (name "CREATEDBY/DATE") "Louis-Daniel Gaulin / 2021-05-01")
        (field (name "VERIFIEDBY") "Philippe Arsenault/2021-05-10")
      )
      (libsource (lib "SWARMUS_LIB") (part "RES_CRCW04023R48FKED"))
    )
    (comp (ref "R152")
      (value "3R48")
      (footprint "RES_0402")
      (description "RES - 3.48 R ±1% 1/16W -  0402")
      (fields
        (field (name "TOLERANCE") "1%")
        (field (name "PACKAGE") "0402")
        (field (name "Comment") "CRCW04023R48FKED")
        (field (name "CREATEDBY/DATE") "Louis-Daniel Gaulin / 2021-05-01")
        (field (name "VERIFIEDBY") "Philippe Arsenault/2021-05-10")
      )
      (libsource (lib "SWARMUS_LIB") (part "RES_CRCW04023R48FKED"))
    )
    (comp (ref "R164")
      (value "33R")
      (footprint "RES_0402")
      (description "RES - 33 OHM 1% 1/16W - 0402")
      (fields
        (field (name "TOLERANCE") "1%")
        (field (name "PACKAGE") "0402")
        (field (name "Comment") "RC0402FR-0733RL")
        (field (name "CREATEDBY/DATE") "Louis-Daniel Gaulin/ 14/01/2020")
        (field (name "VERIFIEDBY") "C.Paulin - 21/01/2020")
      )
      (libsource (lib "GRAMS_MASTER_LIB") (part "RES_RC0402FR-0733RL"))
    )
    (comp (ref "R174")
      (value "33R")
      (footprint "RES_0402")
      (description "RES - 33 OHM 1% 1/16W - 0402")
      (fields
        (field (name "TOLERANCE") "1%")
        (field (name "PACKAGE") "0402")
        (field (name "Comment") "RC0402FR-0733RL")
        (field (name "CREATEDBY/DATE") "Louis-Daniel Gaulin/ 14/01/2020")
        (field (name "VERIFIEDBY") "C.Paulin - 21/01/2020")
      )
      (libsource (lib "GRAMS_MASTER_LIB") (part "RES_RC0402FR-0733RL"))
    )
    (comp (ref "TP6")
      (value "1 MM")
      (footprint "TPO_SMD_ROUND_1MM")
      (description "TPO - TEST POINT ROUND SMD PAD ONLY  - 1 MM")
      (fields
        (field (name "CREATEDBY/DATE") "Jonathan Bouchard 2018-07-17")
        (field (name "VERIFIEDBY") "Arnaud Samson 23-07-18")
      )
      (libsource (lib "GRAMS_MASTER_LIB") (part "TPO_SMD_ROUND_1MM"))
    )
    (comp (ref "TP7")
      (value "1 MM")
      (footprint "TPO_SMD_ROUND_1MM")
      (description "TPO - TEST POINT ROUND SMD PAD ONLY  - 1 MM")
      (fields
        (field (name "CREATEDBY/DATE") "Jonathan Bouchard 2018-07-17")
        (field (name "VERIFIEDBY") "Arnaud Samson 23-07-18")
      )
      (libsource (lib "GRAMS_MASTER_LIB") (part "TPO_SMD_ROUND_1MM"))
    )
    (comp (ref "U10")
      (value "DS90LV001TLD/NOPB")
      (footprint "COM_BUF_DS90LV001TLD/NOPB")
      (description "COM_BUF - ReDriver 1 Channel 800Mbps CML,LVDS,LVPECL to LVDS -  \r\n8-WFDFN EP")
      (fields
        (field (name "CREATEDBY/DATE") "Louis-Daniel Gaulin / 07-04-2021")
        (field (name "VERIFIEDBY") "Philippe Arsenault/2021-04-08")
      )
      (libsource (lib "SWARMUS_LIB") (part "COM_BUF_DS90LV001TLD/NOPB"))
    )
    (comp (ref "U11")
      (value "TC7PZ05FU,LJ(CT")
      (footprint "LOG_BUF_TC7PZ05FU,LJ(CT")
      (description "LOG_BUF - DUAL Buffer inverting Open Drain - SOT-363")
      (fields
        (field (name "CREATEDBY/DATE") "Louis-Daniel Gaulin / 14-04-2021")
        (field (name "VERIFIEDBY") "Philippe Arsenault/2021-04-14")
      )
      (libsource (lib "SWARMUS_LIB") (part "LOG_BUF_TC7PZ05FU,LJ(CT"))
    )
    (comp (ref "U15")
      (value "FIN1027AMX")
      (footprint "COM_XCV_FIN1027AMCOM")
      (description "COM_XCV - 3V3 LVCMOS to LVDS, 2 bits, High-SPEED, DIFF driver - SOIC-8")
      (fields
        (field (name "CREATEDBY/DATE") "Philippe Arsenault/2021-04-01")
        (field (name "VERIFIEDBY") "Louis-Daniel Gaulin - 05/04/2021")
      )
      (libsource (lib "SWARMUS_LIB") (part "COM_XCV_FIN1027AMX"))
    )
    (comp (ref "U16")
      (value "LM339LVRTER")
      (footprint "CMP_LM339LVRTER")
      (description "COMP - Quad Comparator General Purpose Open-Drain, Rail-to-Rail - 16-WQFN (3x3)")
      (fields
        (field (name "CREATEDBY/DATE") "Philippe Arsenault/2021-04-10")
        (field (name "VERIFIEDBY") "Louis-Daniel Gaulin / 14-04-2021")
      )
      (libsource (lib "SWARMUS_LIB") (part "CMP_LM339LVRTER"))
    )
    (comp (ref "U17")
      (value "FIN1028MX")
      (footprint "COM_XCV_FIN1028MX")
      (description "COM_XCV - 3V3 LVDS to LVCMOS, 2 bits, High-SPEED, DIFF receiver - SOIC-8")
      (fields
        (field (name "CREATEDBY/DATE") "Philippe Arsenault/2021-04-01")
        (field (name "VERIFIEDBY") "Louis-Daniel Gaulin - 05/04/2021")
      )
      (libsource (lib "SWARMUS_LIB") (part "COM_XCV_FIN1028MX"))
    )
    (comp (ref "U18")
      (value "74LVC126APW,118")
      (footprint "LOG_BUF_74LVC126APW,118")
      (description "LOG_BUF - Quad Buffer non-inverting 3-States - 14-TSSOP")
      (fields
        (field (name "CREATEDBY/DATE") "Louis-Daniel Gaulin / 11-04-2021")
        (field (name "VERIFIEDBY") "Philippe Arsenault/2021-04-14")
      )
      (libsource (lib "SWARMUS_LIB") (part "LOG_BUF_74LVC126APW,118"))
    )
    (comp (ref "U19")
      (value "FIN1027AMX")
      (footprint "COM_XCV_FIN1027AMCOM")
      (description "COM_XCV - 3V3 LVCMOS to LVDS, 2 bits, High-SPEED, DIFF driver - SOIC-8")
      (fields
        (field (name "CREATEDBY/DATE") "Philippe Arsenault/2021-04-01")
        (field (name "VERIFIEDBY") "Louis-Daniel Gaulin - 05/04/2021")
      )
      (libsource (lib "SWARMUS_LIB") (part "COM_XCV_FIN1027AMX"))
    )
    (comp (ref "U20")
      (value "TC7PZ05FU,LJ(CT")
      (footprint "LOG_BUF_TC7PZ05FU,LJ(CT")
      (description "LOG_BUF - DUAL Buffer inverting Open Drain - SOT-363")
      (fields
        (field (name "CREATEDBY/DATE") "Louis-Daniel Gaulin / 14-04-2021")
        (field (name "VERIFIEDBY") "Philippe Arsenault/2021-04-14")
      )
      (libsource (lib "SWARMUS_LIB") (part "LOG_BUF_TC7PZ05FU,LJ(CT"))
    )
    (comp (ref "U21")
      (value "NIS6150MT1TXG")
      (footprint "POW_NIS6150MT1TXG")
      (description "POW -  Electronic Fuse Regulator 1A -  10-WDFNW")
      (fields
        (field (name "TOLERANCE") "See datasheet")
        (field (name "CREATEDBY/DATE") "Louis-Daniel Gaulin / 29-04-2021")
        (field (name "VERIFIEDBY") "Philippe Arsenault/2021-04-30")
      )
      (libsource (lib "SWARMUS_LIB") (part "POW_NIS6150MT1TXG"))
    )
    (comp (ref "U22")
      (value "DS90LV001TLD/NOPB")
      (footprint "COM_BUF_DS90LV001TLD/NOPB")
      (description "COM_BUF - ReDriver 1 Channel 800Mbps CML,LVDS,LVPECL to LVDS -  \r\n8-WFDFN EP")
      (fields
        (field (name "CREATEDBY/DATE") "Louis-Daniel Gaulin / 07-04-2021")
        (field (name "VERIFIEDBY") "Philippe Arsenault/2021-04-08")
      )
      (libsource (lib "SWARMUS_LIB") (part "COM_BUF_DS90LV001TLD/NOPB"))
    )
    (comp (ref "U23")
      (value "74LVC1G11DW-7")
      (footprint "LOG_AND_74LVC1G11DW-7")
      (description "LOG - AND Gate, 1CH 3-INP - 6-TSSOP")
      (fields
        (field (name "CREATEDBY/DATE") "Louis-Daniel Gaulin / 26-02-2020")
        (field (name "VERIFIEDBY") "C.Paulin - 9/03/2020")
      )
      (libsource (lib "GRAMS_MASTER_LIB") (part "LOG_AND_74LVC1G11DW-7"))
    )
    (comp (ref "U25")
      (value "74LVC1G11DW-7")
      (footprint "LOG_AND_74LVC1G11DW-7")
      (description "LOG - AND Gate, 1CH 3-INP - 6-TSSOP")
      (fields
        (field (name "CREATEDBY/DATE") "Louis-Daniel Gaulin / 26-02-2020")
        (field (name "VERIFIEDBY") "C.Paulin - 9/03/2020")
      )
      (libsource (lib "GRAMS_MASTER_LIB") (part "LOG_AND_74LVC1G11DW-7"))
    )
    (comp (ref "U27")
      (value "NIS6150MT1TXG")
      (footprint "POW_NIS6150MT1TXG")
      (description "POW -  Electronic Fuse Regulator 1A -  10-WDFNW")
      (fields
        (field (name "TOLERANCE") "See datasheet")
        (field (name "CREATEDBY/DATE") "Louis-Daniel Gaulin / 29-04-2021")
        (field (name "VERIFIEDBY") "Philippe Arsenault/2021-04-30")
      )
      (libsource (lib "SWARMUS_LIB") (part "POW_NIS6150MT1TXG"))
    )
    (comp (ref "U28")
      (value "74AHC1G07GV,125")
      (footprint "LOG_BUF_ 74AHC1G07GV,125")
      (description "LOG_BUF - Buffer non-inverting Open Drain - SC-74A")
      (fields
        (field (name "CREATEDBY/DATE") "Louis-Daniel Gaulin / 07-04-2021")
        (field (name "VERIFIEDBY") "Philippe Arsenault/2021-04-08")
      )
      (libsource (lib "SWARMUS_LIB") (part "LOG_BUF_74AHC1G07GV,125"))
    )
    (comp (ref "U29")
      (value "74AHC1G07GV,125")
      (footprint "LOG_BUF_ 74AHC1G07GV,125")
      (description "LOG_BUF - Buffer non-inverting Open Drain - SC-74A")
      (fields
        (field (name "CREATEDBY/DATE") "Louis-Daniel Gaulin / 07-04-2021")
        (field (name "VERIFIEDBY") "Philippe Arsenault/2021-04-08")
      )
      (libsource (lib "SWARMUS_LIB") (part "LOG_BUF_74AHC1G07GV,125"))
    )
    (comp (ref "U34")
      (value "74LVC1G126GV,125")
      (footprint "LOG_BUF_ 74LVC1G126GV,125")
      (description "LOG_BUF - Buffer non-inverting 3-States - SC-74A")
      (fields
        (field (name "CREATEDBY/DATE") "Philippe Arsenault/2021-04-08")
        (field (name "VERIFIEDBY") "Louis-Daniel Gaulin / 11-04-2021")
      )
      (libsource (lib "SWARMUS_LIB") (part "LOG_BUF_74LVC1G126GV,125"))
    )
    (comp (ref "U35")
      (value "74LVC1G126GV,125")
      (footprint "LOG_BUF_ 74LVC1G126GV,125")
      (description "LOG_BUF - Buffer non-inverting 3-States - SC-74A")
      (fields
        (field (name "CREATEDBY/DATE") "Philippe Arsenault/2021-04-08")
        (field (name "VERIFIEDBY") "Louis-Daniel Gaulin / 11-04-2021")
      )
      (libsource (lib "SWARMUS_LIB") (part "LOG_BUF_74LVC1G126GV,125"))
    )
    (comp (ref "U36")
      (value "74LVC1G04GV")
      (footprint "LOG_INV_74LVC1G04GV")
      (description "LOG - INVERTER 1CH 1-INP - SOT-753")
      (fields
        (field (name "CREATEDBY/DATE") "Keven Deslandes - 2018-09-12")
        (field (name "VERIFIEDBY") "Caroline Paulin - 17/12/2018")
      )
      (libsource (lib "GRAMS_MASTER_LIB") (part "LOG_INV_74LVC1G04GV"))
    )
    (comp (ref "U37")
      (value "74LVC1G04GV")
      (footprint "LOG_INV_74LVC1G04GV")
      (description "LOG - INVERTER 1CH 1-INP - SOT-753")
      (fields
        (field (name "CREATEDBY/DATE") "Keven Deslandes - 2018-09-12")
        (field (name "VERIFIEDBY") "Caroline Paulin - 17/12/2018")
      )
      (libsource (lib "GRAMS_MASTER_LIB") (part "LOG_INV_74LVC1G04GV"))
    )
  )
  (nets
    (net (code "1") (name "/BB_CC1_0") (class "Default")
      (node (ref "J4") (pin "A5") (pinfunction "CC1_A5") (pintype "passive"))
      (node (ref "R95") (pin "2") (pinfunction "2_2") (pintype "passive"))
      (node (ref "U11") (pin "1") (pinfunction "1A_1") (pintype "passive"))
    )
    (net (code "2") (name "/BB_CC1_1") (class "Default")
      (node (ref "J5") (pin "A5") (pinfunction "CC1_A5") (pintype "passive"))
      (node (ref "R117") (pin "2") (pinfunction "2_2") (pintype "passive"))
      (node (ref "U20") (pin "1") (pinfunction "1A_1") (pintype "passive"))
    )
    (net (code "3") (name "/BB_CC2_0") (class "Default")
      (node (ref "J4") (pin "B5") (pinfunction "CC2_B5") (pintype "passive"))
      (node (ref "R97") (pin "1") (pinfunction "1_1") (pintype "passive"))
      (node (ref "U11") (pin "3") (pinfunction "2A_3") (pintype "passive"))
    )
    (net (code "4") (name "/BB_CC2_1") (class "Default")
      (node (ref "J5") (pin "B5") (pinfunction "CC2_B5") (pintype "passive"))
      (node (ref "R118") (pin "1") (pinfunction "1_1") (pintype "passive"))
      (node (ref "U20") (pin "3") (pinfunction "2A_3") (pintype "passive"))
    )
    (net (code "5") (name "/BB_CLK_0_N") (class "Default")
      (node (ref "D8") (pin "5") (pinfunction "IO4_5") (pintype "passive"))
      (node (ref "D8") (pin "6") (pinfunction "NC_6") (pintype "passive"))
      (node (ref "J4") (pin "A3") (pinfunction "TX1-_A3") (pintype "passive"))
      (node (ref "U10") (pin "7") (pinfunction "OUT-_7") (pintype "passive"))
    )
    (net (code "6") (name "/BB_CLK_0_P") (class "Default")
      (node (ref "D8") (pin "4") (pinfunction "IO3_4") (pintype "passive"))
      (node (ref "D8") (pin "7") (pinfunction "NC_7") (pintype "passive"))
      (node (ref "J4") (pin "A2") (pinfunction "TX1+_A2") (pintype "passive"))
      (node (ref "U10") (pin "6") (pinfunction "OUT+_6") (pintype "passive"))
    )
    (net (code "7") (name "/BB_CLK_1_N") (class "Default")
      (node (ref "D21") (pin "5") (pinfunction "IO4_5") (pintype "passive"))
      (node (ref "D21") (pin "6") (pinfunction "NC_6") (pintype "passive"))
      (node (ref "J5") (pin "A3") (pinfunction "TX1-_A3") (pintype "passive"))
      (node (ref "U22") (pin "7") (pinfunction "OUT-_7") (pintype "passive"))
    )
    (net (code "8") (name "/BB_CLK_1_P") (class "Default")
      (node (ref "D21") (pin "4") (pinfunction "IO3_4") (pintype "passive"))
      (node (ref "D21") (pin "7") (pinfunction "NC_7") (pintype "passive"))
      (node (ref "J5") (pin "A2") (pinfunction "TX1+_A2") (pintype "passive"))
      (node (ref "U22") (pin "6") (pinfunction "OUT+_6") (pintype "passive"))
    )
    (net (code "9") (name "/BB_RESET_0") (class "Default")
      (node (ref "D9") (pin "5") (pinfunction "IO4_5") (pintype "passive"))
      (node (ref "D9") (pin "6") (pinfunction "NC_6") (pintype "passive"))
      (node (ref "J4") (pin "A8") (pinfunction "SBU1_A8") (pintype "passive"))
      (node (ref "R99") (pin "2") (pinfunction "2_2") (pintype "passive"))
      (node (ref "U16") (pin "9") (pinfunction "IN4-_9") (pintype "passive"))
      (node (ref "U18") (pin "6") (pinfunction "2Y_6") (pintype "passive"))
    )
    (net (code "10") (name "/BB_RESET_1") (class "Default")
      (node (ref "D15") (pin "5") (pinfunction "IO4_5") (pintype "passive"))
      (node (ref "D15") (pin "6") (pinfunction "NC_6") (pintype "passive"))
      (node (ref "J5") (pin "A8") (pinfunction "SBU1_A8") (pintype "passive"))
      (node (ref "R119") (pin "2") (pinfunction "2_2") (pintype "passive"))
      (node (ref "U16") (pin "2") (pinfunction "IN1-_2") (pintype "passive"))
      (node (ref "U18") (pin "11") (pinfunction "4Y_11") (pintype "passive"))
    )
    (net (code "11") (name "/BB_SPI_CLK_0_N") (class "Default")
      (node (ref "D8") (pin "1") (pinfunction "IO1_1") (pintype "passive"))
      (node (ref "D8") (pin "10") (pinfunction "NC_10") (pintype "passive"))
      (node (ref "J4") (pin "B10") (pinfunction "RX1-_B10") (pintype "passive"))
      (node (ref "U15") (pin "5") (pinfunction "Dout_2-_5") (pintype "passive"))
    )
    (net (code "12") (name "/BB_SPI_CLK_0_P") (class "Default")
      (node (ref "D8") (pin "2") (pinfunction "IO2_2") (pintype "passive"))
      (node (ref "D8") (pin "9") (pinfunction "NC_9") (pintype "passive"))
      (node (ref "J4") (pin "B11") (pinfunction "RX1+_B11") (pintype "passive"))
      (node (ref "U15") (pin "6") (pinfunction "Dout_2+_6") (pintype "passive"))
    )
    (net (code "13") (name "/BB_SPI_CLK_1_N") (class "Default")
      (node (ref "D21") (pin "1") (pinfunction "IO1_1") (pintype "passive"))
      (node (ref "D21") (pin "10") (pinfunction "NC_10") (pintype "passive"))
      (node (ref "J5") (pin "B10") (pinfunction "RX1-_B10") (pintype "passive"))
      (node (ref "U19") (pin "5") (pinfunction "Dout_2-_5") (pintype "passive"))
    )
    (net (code "14") (name "/BB_SPI_CLK_1_P") (class "Default")
      (node (ref "D21") (pin "2") (pinfunction "IO2_2") (pintype "passive"))
      (node (ref "D21") (pin "9") (pinfunction "NC_9") (pintype "passive"))
      (node (ref "J5") (pin "B11") (pinfunction "RX1+_B11") (pintype "passive"))
      (node (ref "U19") (pin "6") (pinfunction "Dout_2+_6") (pintype "passive"))
    )
    (net (code "15") (name "/BB_SPI_MISO_0_N") (class "Default")
      (node (ref "D9") (pin "2") (pinfunction "IO2_2") (pintype "passive"))
      (node (ref "D9") (pin "9") (pinfunction "NC_9") (pintype "passive"))
      (node (ref "J4") (pin "A7") (pinfunction "D-_A7") (pintype "passive"))
      (node (ref "J4") (pin "B7") (pinfunction "D-_B7") (pintype "passive"))
      (node (ref "R104") (pin "1") (pinfunction "1_1") (pintype "passive"))
      (node (ref "U17") (pin "4") (pinfunction "Rin_2-_4") (pintype "passive"))
    )
    (net (code "16") (name "/BB_SPI_MISO_0_P") (class "Default")
      (node (ref "D9") (pin "1") (pinfunction "IO1_1") (pintype "passive"))
      (node (ref "D9") (pin "10") (pinfunction "NC_10") (pintype "passive"))
      (node (ref "J4") (pin "A6") (pinfunction "D+_A6") (pintype "passive"))
      (node (ref "J4") (pin "B6") (pinfunction "D+_B6") (pintype "passive"))
      (node (ref "R104") (pin "2") (pinfunction "2_2") (pintype "passive"))
      (node (ref "U17") (pin "3") (pinfunction "Rin_2+_3") (pintype "passive"))
    )
    (net (code "17") (name "/BB_SPI_MISO_1_N") (class "Default")
      (node (ref "D15") (pin "2") (pinfunction "IO2_2") (pintype "passive"))
      (node (ref "D15") (pin "9") (pinfunction "NC_9") (pintype "passive"))
      (node (ref "J5") (pin "A7") (pinfunction "D-_A7") (pintype "passive"))
      (node (ref "J5") (pin "B7") (pinfunction "D-_B7") (pintype "passive"))
      (node (ref "R103") (pin "2") (pinfunction "2_2") (pintype "passive"))
      (node (ref "U17") (pin "1") (pinfunction "Rin_1-_1") (pintype "passive"))
    )
    (net (code "18") (name "/BB_SPI_MISO_1_P") (class "Default")
      (node (ref "D15") (pin "1") (pinfunction "IO1_1") (pintype "passive"))
      (node (ref "D15") (pin "10") (pinfunction "NC_10") (pintype "passive"))
      (node (ref "J5") (pin "A6") (pinfunction "D+_A6") (pintype "passive"))
      (node (ref "J5") (pin "B6") (pinfunction "D+_B6") (pintype "passive"))
      (node (ref "R103") (pin "1") (pinfunction "1_1") (pintype "passive"))
      (node (ref "U17") (pin "2") (pinfunction "Rin_1+_2") (pintype "passive"))
    )
    (net (code "19") (name "/BB_SPI_MOSI_0_N") (class "Default")
      (node (ref "D10") (pin "1") (pinfunction "IO1_1") (pintype "passive"))
      (node (ref "D10") (pin "10") (pinfunction "NC_10") (pintype "passive"))
      (node (ref "J4") (pin "A10") (pinfunction "RX2-_A10") (pintype "passive"))
      (node (ref "U15") (pin "8") (pinfunction "Dout_1-_8") (pintype "passive"))
    )
    (net (code "20") (name "/BB_SPI_MOSI_0_P") (class "Default")
      (node (ref "D10") (pin "2") (pinfunction "IO2_2") (pintype "passive"))
      (node (ref "D10") (pin "9") (pinfunction "NC_9") (pintype "passive"))
      (node (ref "J4") (pin "A11") (pinfunction "RX2+_A11") (pintype "passive"))
      (node (ref "U15") (pin "7") (pinfunction "Dout_1+_7") (pintype "passive"))
    )
    (net (code "21") (name "/BB_SPI_MOSI_1_N") (class "Default")
      (node (ref "D18") (pin "1") (pinfunction "IO1_1") (pintype "passive"))
      (node (ref "D18") (pin "10") (pinfunction "NC_10") (pintype "passive"))
      (node (ref "J5") (pin "A10") (pinfunction "RX2-_A10") (pintype "passive"))
      (node (ref "U19") (pin "8") (pinfunction "Dout_1-_8") (pintype "passive"))
    )
    (net (code "22") (name "/BB_SPI_MOSI_1_P") (class "Default")
      (node (ref "D18") (pin "2") (pinfunction "IO2_2") (pintype "passive"))
      (node (ref "D18") (pin "9") (pinfunction "NC_9") (pintype "passive"))
      (node (ref "J5") (pin "A11") (pinfunction "RX2+_A11") (pintype "passive"))
      (node (ref "U19") (pin "7") (pinfunction "Dout_1+_7") (pintype "passive"))
    )
    (net (code "23") (name "/BB_SPI_nCS_0") (class "Default")
      (node (ref "D9") (pin "4") (pinfunction "IO3_4") (pintype "passive"))
      (node (ref "D9") (pin "7") (pinfunction "NC_7") (pintype "passive"))
      (node (ref "J4") (pin "B8") (pinfunction "SBU2_B8") (pintype "passive"))
      (node (ref "U18") (pin "3") (pinfunction "1Y_3") (pintype "passive"))
    )
    (net (code "24") (name "/BB_SPI_nCS_1") (class "Default")
      (node (ref "D15") (pin "4") (pinfunction "IO3_4") (pintype "passive"))
      (node (ref "D15") (pin "7") (pinfunction "NC_7") (pintype "passive"))
      (node (ref "J5") (pin "B8") (pinfunction "SBU2_B8") (pintype "passive"))
      (node (ref "U18") (pin "8") (pinfunction "3Y_8") (pintype "passive"))
    )
    (net (code "25") (name "/BB_VIN_0") (class "Default")
      (node (ref "C141") (pin "2") (pinfunction "2_2") (pintype "passive"))
      (node (ref "D11") (pin "1") (pinfunction "1_1") (pintype "passive"))
      (node (ref "J4") (pin "A4") (pinfunction "VBUS_A4") (pintype "passive"))
      (node (ref "J4") (pin "A9") (pinfunction "VBUS_A9") (pintype "passive"))
      (node (ref "J4") (pin "B4") (pinfunction "VBUS_B4") (pintype "passive"))
      (node (ref "J4") (pin "B9") (pinfunction "VBUS_B9") (pintype "passive"))
      (node (ref "R151") (pin "1") (pinfunction "1_1") (pintype "passive"))
      (node (ref "TP6") (pin "1") (pinfunction "1_1") (pintype "passive"))
      (node (ref "U27") (pin "10") (pinfunction "Source_10") (pintype "passive"))
      (node (ref "U27") (pin "9") (pinfunction "Source_9") (pintype "passive"))
    )
    (net (code "26") (name "/BB_VIN_1") (class "Default")
      (node (ref "C127") (pin "2") (pinfunction "2_2") (pintype "passive"))
      (node (ref "D16") (pin "1") (pinfunction "1_1") (pintype "passive"))
      (node (ref "J5") (pin "A4") (pinfunction "VBUS_A4") (pintype "passive"))
      (node (ref "J5") (pin "A9") (pinfunction "VBUS_A9") (pintype "passive"))
      (node (ref "J5") (pin "B4") (pinfunction "VBUS_B4") (pintype "passive"))
      (node (ref "J5") (pin "B9") (pinfunction "VBUS_B9") (pintype "passive"))
      (node (ref "R152") (pin "1") (pinfunction "1_1") (pintype "passive"))
      (node (ref "TP7") (pin "1") (pinfunction "1_1") (pintype "passive"))
      (node (ref "U21") (pin "10") (pinfunction "Source_10") (pintype "passive"))
      (node (ref "U21") (pin "9") (pinfunction "Source_9") (pintype "passive"))
    )
    (net (code "27") (name "/CHAN_DET_0") (class "Default")
      (node (ref "R113") (pin "2") (pinfunction "2_2") (pintype "passive"))
      (node (ref "U16") (pin "13") (pinfunction "OUT4_13") (pintype "passive"))
    )
    (net (code "28") (name "/CHAN_DET_1") (class "Default")
      (node (ref "R124") (pin "2") (pinfunction "2_2") (pintype "passive"))
      (node (ref "U16") (pin "16") (pinfunction "OUT1_16") (pintype "passive"))
    )
    (net (code "29") (name "/CHAN_EN_0") (class "Default")
      (node (ref "U23") (pin "6") (pinfunction "C_6") (pintype "passive"))
    )
    (net (code "30") (name "/CHAN_EN_1") (class "Default")
      (node (ref "U25") (pin "6") (pinfunction "C_6") (pintype "passive"))
    )
    (net (code "31") (name "/CHAN_FLAG_0") (class "Default")
      (node (ref "U27") (pin "6") (pinfunction "FLAG_6") (pintype "passive"))
      (node (ref "U28") (pin "2") (pinfunction "A_2") (pintype "passive"))
    )
    (net (code "32") (name "/CHAN_FLAG_1") (class "Default")
      (node (ref "U21") (pin "6") (pinfunction "FLAG_6") (pintype "passive"))
      (node (ref "U29") (pin "2") (pinfunction "A_2") (pintype "passive"))
    )
    (net (code "33") (name "/CHAN_FLT#_0") (class "Default")
      (node (ref "D14") (pin "K") (pinfunction "K_K") (pintype "passive"))
      (node (ref "U28") (pin "4") (pinfunction "Y_4") (pintype "passive"))
    )
    (net (code "34") (name "/CHAN_FLT#_1") (class "Default")
      (node (ref "D20") (pin "K") (pinfunction "K_K") (pintype "passive"))
      (node (ref "U29") (pin "4") (pinfunction "Y_4") (pintype "passive"))
    )
    (net (code "35") (name "/CHAN_IRQ_0") (class "Default")
      (node (ref "R93") (pin "2") (pinfunction "2_2") (pintype "passive"))
      (node (ref "U11") (pin "4") (pinfunction "2Y_4") (pintype "passive"))
      (node (ref "U11") (pin "6") (pinfunction "1Y_6") (pintype "passive"))
    )
    (net (code "36") (name "/CHAN_IRQ_1") (class "Default")
      (node (ref "R112") (pin "2") (pinfunction "2_2") (pintype "passive"))
      (node (ref "U20") (pin "4") (pinfunction "2Y_4") (pintype "passive"))
      (node (ref "U20") (pin "6") (pinfunction "1Y_6") (pintype "passive"))
    )
    (net (code "37") (name "/CHAN_OV_0") (class "Default")
      (node (ref "R105") (pin "2") (pinfunction "2_2") (pintype "passive"))
      (node (ref "R111") (pin "2") (pinfunction "2_2") (pintype "passive"))
      (node (ref "U23") (pin "3") (pinfunction "B_3") (pintype "passive"))
    )
    (net (code "38") (name "/CHAN_OV_1") (class "Default")
      (node (ref "R101") (pin "2") (pinfunction "2_2") (pintype "passive"))
      (node (ref "R102") (pin "2") (pinfunction "2_2") (pintype "passive"))
      (node (ref "U25") (pin "3") (pinfunction "B_3") (pintype "passive"))
    )
    (net (code "39") (name "/CHAN_RESET_0") (class "Default")
      (node (ref "U18") (pin "5") (pinfunction "2A_5") (pintype "passive"))
    )
    (net (code "40") (name "/CHAN_RESET_1") (class "Default")
      (node (ref "U18") (pin "12") (pinfunction "4A_12") (pintype "passive"))
    )
    (net (code "41") (name "/CLK_0_N") (class "Default")
      (node (ref "R94") (pin "1") (pinfunction "1_1") (pintype "passive"))
      (node (ref "U10") (pin "2") (pinfunction "IN-_2") (pintype "passive"))
    )
    (net (code "42") (name "/CLK_0_P") (class "Default")
      (node (ref "R94") (pin "2") (pinfunction "2_2") (pintype "passive"))
      (node (ref "U10") (pin "3") (pinfunction "IN+_3") (pintype "passive"))
    )
    (net (code "43") (name "/CLK_1_N") (class "Default")
      (node (ref "R128") (pin "1") (pinfunction "1_1") (pintype "passive"))
      (node (ref "U22") (pin "2") (pinfunction "IN-_2") (pintype "passive"))
    )
    (net (code "44") (name "/CLK_1_P") (class "Default")
      (node (ref "R128") (pin "2") (pinfunction "2_2") (pintype "passive"))
      (node (ref "U22") (pin "3") (pinfunction "IN+_3") (pintype "passive"))
    )
    (net (code "45") (name "/HW_EN_0") (class "Default")
      (node (ref "Q3") (pin "1") (pinfunction "G_1") (pintype "passive"))
      (node (ref "U10") (pin "8") (pinfunction "EN_8") (pintype "passive"))
      (node (ref "U18") (pin "1") (pinfunction "1OE_1") (pintype "passive"))
      (node (ref "U18") (pin "4") (pinfunction "2OE_4") (pintype "passive"))
      (node (ref "U23") (pin "4") (pinfunction "Y_4") (pintype "passive"))
      (node (ref "U27") (pin "7") (pinfunction "EN_7") (pintype "passive"))
    )
    (net (code "46") (name "/HW_EN_1") (class "Default")
      (node (ref "Q4") (pin "1") (pinfunction "G_1") (pintype "passive"))
      (node (ref "U18") (pin "10") (pinfunction "3OE_10") (pintype "passive"))
      (node (ref "U18") (pin "13") (pinfunction "4OE_13") (pintype "passive"))
      (node (ref "U21") (pin "7") (pinfunction "EN_7") (pintype "passive"))
      (node (ref "U22") (pin "8") (pinfunction "EN_8") (pintype "passive"))
      (node (ref "U25") (pin "4") (pinfunction "Y_4") (pintype "passive"))
    )
    (net (code "47") (name "/SPI_CLK") (class "Default")
      (node (ref "U15") (pin "2") (pinfunction "Din_1_2") (pintype "passive"))
      (node (ref "U19") (pin "2") (pinfunction "Din_1_2") (pintype "passive"))
    )
    (net (code "48") (name "/SPI_CS_0") (class "Default")
      (node (ref "U34") (pin "1") (pinfunction "OE_1") (pintype "passive"))
      (node (ref "U36") (pin "4") (pinfunction "Y_4") (pintype "passive"))
    )
    (net (code "49") (name "/SPI_CS_1") (class "Default")
      (node (ref "U35") (pin "1") (pinfunction "OE_1") (pintype "passive"))
      (node (ref "U37") (pin "4") (pinfunction "Y_4") (pintype "passive"))
    )
    (net (code "50") (name "/SPI_MISO") (class "Default")
      (node (ref "R164") (pin "2") (pinfunction "2_2") (pintype "passive"))
      (node (ref "R174") (pin "2") (pinfunction "2_2") (pintype "passive"))
    )
    (net (code "51") (name "/SPI_MISO_0") (class "Default")
      (node (ref "U17") (pin "7") (pinfunction "Rout_1_7") (pintype "passive"))
      (node (ref "U34") (pin "2") (pinfunction "A_2") (pintype "passive"))
    )
    (net (code "52") (name "/SPI_MISO_1") (class "Default")
      (node (ref "U17") (pin "6") (pinfunction "Rout_2_6") (pintype "passive"))
      (node (ref "U35") (pin "2") (pinfunction "A_2") (pintype "passive"))
    )
    (net (code "53") (name "/SPI_MOSI") (class "Default")
      (node (ref "U15") (pin "3") (pinfunction "Din_2_3") (pintype "passive"))
      (node (ref "U19") (pin "3") (pinfunction "Din_2_3") (pintype "passive"))
    )
    (net (code "54") (name "/SPI_nCS_0") (class "Default")
      (node (ref "U18") (pin "2") (pinfunction "1A_2") (pintype "passive"))
      (node (ref "U36") (pin "2") (pinfunction "A_2") (pintype "passive"))
    )
    (net (code "55") (name "/SPI_nCS_1") (class "Default")
      (node (ref "U18") (pin "9") (pinfunction "3A_9") (pintype "passive"))
      (node (ref "U37") (pin "2") (pinfunction "A_2") (pintype "passive"))
    )
    (net (code "56") (name "/SYNC_0_N") (class "Default")
      (node (ref "D10") (pin "5") (pinfunction "IO4_5") (pintype "passive"))
      (node (ref "D10") (pin "6") (pinfunction "NC_6") (pintype "passive"))
      (node (ref "J4") (pin "B3") (pinfunction "TX2-_B3") (pintype "passive"))
    )
    (net (code "57") (name "/SYNC_0_P") (class "Default")
      (node (ref "D10") (pin "4") (pinfunction "IO3_4") (pintype "passive"))
      (node (ref "D10") (pin "7") (pinfunction "NC_7") (pintype "passive"))
      (node (ref "J4") (pin "B2") (pinfunction "TX2+_B2") (pintype "passive"))
    )
    (net (code "58") (name "/SYNC_1_N") (class "Default")
      (node (ref "D18") (pin "5") (pinfunction "IO4_5") (pintype "passive"))
      (node (ref "D18") (pin "6") (pinfunction "NC_6") (pintype "passive"))
      (node (ref "J5") (pin "B3") (pinfunction "TX2-_B3") (pintype "passive"))
    )
    (net (code "59") (name "/SYNC_1_P") (class "Default")
      (node (ref "D18") (pin "4") (pinfunction "IO3_4") (pintype "passive"))
      (node (ref "D18") (pin "7") (pinfunction "NC_7") (pintype "passive"))
      (node (ref "J5") (pin "B2") (pinfunction "TX2+_B2") (pintype "passive"))
    )
    (net (code "60") (name "3V3") (class "Default")
      (node (ref "C117") (pin "2") (pinfunction "2_2") (pintype "passive"))
      (node (ref "C128") (pin "2") (pinfunction "2_2") (pintype "passive"))
      (node (ref "C133") (pin "2") (pinfunction "2_2") (pintype "passive"))
      (node (ref "R100") (pin "1") (pinfunction "1_1") (pintype "passive"))
      (node (ref "R101") (pin "1") (pinfunction "1_1") (pintype "passive"))
      (node (ref "R110") (pin "2") (pinfunction "2_2") (pintype "passive"))
      (node (ref "R111") (pin "1") (pinfunction "1_1") (pintype "passive"))
      (node (ref "R113") (pin "1") (pinfunction "1_1") (pintype "passive"))
      (node (ref "R115") (pin "2") (pinfunction "2_2") (pintype "passive"))
      (node (ref "R123") (pin "2") (pinfunction "2_2") (pintype "passive"))
      (node (ref "R124") (pin "1") (pinfunction "1_1") (pintype "passive"))
      (node (ref "R77") (pin "2") (pinfunction "2_2") (pintype "passive"))
      (node (ref "U16") (pin "1") (pinfunction "V+_1") (pintype "passive"))
      (node (ref "U23") (pin "5") (pinfunction "VCC_5") (pintype "passive"))
      (node (ref "U25") (pin "5") (pinfunction "VCC_5") (pintype "passive"))
    )
    (net (code "61") (name "3V3_CH") (class "Default")
      (node (ref "C108") (pin "2") (pinfunction "2_2") (pintype "passive"))
      (node (ref "C109") (pin "2") (pinfunction "2_2") (pintype "passive"))
      (node (ref "C110") (pin "1") (pinfunction "1_1") (pintype "passive"))
      (node (ref "C113") (pin "2") (pinfunction "2_2") (pintype "passive"))
      (node (ref "C114") (pin "1") (pinfunction "1_1") (pintype "passive"))
      (node (ref "C115") (pin "1") (pinfunction "1_1") (pintype "passive"))
      (node (ref "C118") (pin "1") (pinfunction "1_1") (pintype "passive"))
      (node (ref "C119") (pin "1") (pinfunction "1_1") (pintype "passive"))
      (node (ref "C120") (pin "1") (pinfunction "1_1") (pintype "passive"))
      (node (ref "C121") (pin "1") (pinfunction "1_1") (pintype "passive"))
      (node (ref "C122") (pin "1") (pinfunction "1_1") (pintype "passive"))
      (node (ref "C125") (pin "2") (pinfunction "2_2") (pintype "passive"))
      (node (ref "C126") (pin "2") (pinfunction "2_2") (pintype "passive"))
      (node (ref "C145") (pin "1") (pinfunction "1_1") (pintype "passive"))
      (node (ref "C146") (pin "1") (pinfunction "1_1") (pintype "passive"))
      (node (ref "C150") (pin "1") (pinfunction "1_1") (pintype "passive"))
      (node (ref "C151") (pin "1") (pinfunction "1_1") (pintype "passive"))
      (node (ref "R112") (pin "1") (pinfunction "1_1") (pintype "passive"))
      (node (ref "R117") (pin "1") (pinfunction "1_1") (pintype "passive"))
      (node (ref "R119") (pin "1") (pinfunction "1_1") (pintype "passive"))
      (node (ref "R93") (pin "1") (pinfunction "1_1") (pintype "passive"))
      (node (ref "R95") (pin "1") (pinfunction "1_1") (pintype "passive"))
      (node (ref "R99") (pin "1") (pinfunction "1_1") (pintype "passive"))
      (node (ref "U10") (pin "5") (pinfunction "VCC_5") (pintype "passive"))
      (node (ref "U11") (pin "5") (pinfunction "VCC_5") (pintype "passive"))
      (node (ref "U15") (pin "1") (pinfunction "VCC_1") (pintype "passive"))
      (node (ref "U17") (pin "8") (pinfunction "VCC_8") (pintype "passive"))
      (node (ref "U18") (pin "14") (pinfunction "VCC_14") (pintype "passive"))
      (node (ref "U19") (pin "1") (pinfunction "VCC_1") (pintype "passive"))
      (node (ref "U20") (pin "5") (pinfunction "VCC_5") (pintype "passive"))
      (node (ref "U22") (pin "5") (pinfunction "VCC_5") (pintype "passive"))
      (node (ref "U23") (pin "1") (pinfunction "A_1") (pintype "passive"))
      (node (ref "U25") (pin "1") (pinfunction "A_1") (pintype "passive"))
      (node (ref "U34") (pin "5") (pinfunction "VCC_5") (pintype "passive"))
      (node (ref "U35") (pin "5") (pinfunction "VCC_5") (pintype "passive"))
      (node (ref "U36") (pin "5") (pinfunction "VCC_5") (pintype "passive"))
      (node (ref "U37") (pin "5") (pinfunction "VCC_5") (pintype "passive"))
    )
    (net (code "62") (name "5V") (class "Default")
      (node (ref "C111") (pin "1") (pinfunction "1_1") (pintype "passive"))
      (node (ref "C124") (pin "2") (pinfunction "2_2") (pintype "passive"))
      (node (ref "C139") (pin "1") (pinfunction "1_1") (pintype "passive"))
      (node (ref "C140") (pin "2") (pinfunction "2_2") (pintype "passive"))
      (node (ref "R107") (pin "1") (pinfunction "1_1") (pintype "passive"))
      (node (ref "U21") (pin "1") (pinfunction "VCC_1") (pintype "passive"))
      (node (ref "U21") (pin "2") (pinfunction "VCC_2") (pintype "passive"))
      (node (ref "U27") (pin "1") (pinfunction "VCC_1") (pintype "passive"))
      (node (ref "U27") (pin "2") (pinfunction "VCC_2") (pintype "passive"))
      (node (ref "U28") (pin "5") (pinfunction "VCC_5") (pintype "passive"))
      (node (ref "U29") (pin "5") (pinfunction "VCC_5") (pintype "passive"))
    )
    (net (code "63") (name "GND") (class "Default")
      (node (ref "C108") (pin "1") (pinfunction "1_1") (pintype "passive"))
      (node (ref "C109") (pin "1") (pinfunction "1_1") (pintype "passive"))
      (node (ref "C110") (pin "2") (pinfunction "2_2") (pintype "passive"))
      (node (ref "C111") (pin "2") (pinfunction "2_2") (pintype "passive"))
      (node (ref "C113") (pin "1") (pinfunction "1_1") (pintype "passive"))
      (node (ref "C114") (pin "2") (pinfunction "2_2") (pintype "passive"))
      (node (ref "C115") (pin "2") (pinfunction "2_2") (pintype "passive"))
      (node (ref "C117") (pin "1") (pinfunction "1_1") (pintype "passive"))
      (node (ref "C118") (pin "2") (pinfunction "2_2") (pintype "passive"))
      (node (ref "C119") (pin "2") (pinfunction "2_2") (pintype "passive"))
      (node (ref "C120") (pin "2") (pinfunction "2_2") (pintype "passive"))
      (node (ref "C121") (pin "2") (pinfunction "2_2") (pintype "passive"))
      (node (ref "C122") (pin "2") (pinfunction "2_2") (pintype "passive"))
      (node (ref "C124") (pin "1") (pinfunction "1_1") (pintype "passive"))
      (node (ref "C125") (pin "1") (pinfunction "1_1") (pintype "passive"))
      (node (ref "C126") (pin "1") (pinfunction "1_1") (pintype "passive"))
      (node (ref "C127") (pin "1") (pinfunction "1_1") (pintype "passive"))
      (node (ref "C128") (pin "1") (pinfunction "1_1") (pintype "passive"))
      (node (ref "C133") (pin "1") (pinfunction "1_1") (pintype "passive"))
      (node (ref "C139") (pin "2") (pinfunction "2_2") (pintype "passive"))
      (node (ref "C140") (pin "1") (pinfunction "1_1") (pintype "passive"))
      (node (ref "C141") (pin "1") (pinfunction "1_1") (pintype "passive"))
      (node (ref "C145") (pin "2") (pinfunction "2_2") (pintype "passive"))
      (node (ref "C146") (pin "2") (pinfunction "2_2") (pintype "passive"))
      (node (ref "C150") (pin "2") (pinfunction "2_2") (pintype "passive"))
      (node (ref "C151") (pin "2") (pinfunction "2_2") (pintype "passive"))
      (node (ref "D10") (pin "3") (pinfunction "VSS_3") (pintype "passive"))
      (node (ref "D10") (pin "8") (pinfunction "VSS_8") (pintype "passive"))
      (node (ref "D11") (pin "2") (pinfunction "2_2") (pintype "passive"))
      (node (ref "D15") (pin "3") (pinfunction "VSS_3") (pintype "passive"))
      (node (ref "D15") (pin "8") (pinfunction "VSS_8") (pintype "passive"))
      (node (ref "D16") (pin "2") (pinfunction "2_2") (pintype "passive"))
      (node (ref "D18") (pin "3") (pinfunction "VSS_3") (pintype "passive"))
      (node (ref "D18") (pin "8") (pinfunction "VSS_8") (pintype "passive"))
      (node (ref "D21") (pin "3") (pinfunction "VSS_3") (pintype "passive"))
      (node (ref "D21") (pin "8") (pinfunction "VSS_8") (pintype "passive"))
      (node (ref "D8") (pin "3") (pinfunction "VSS_3") (pintype "passive"))
      (node (ref "D8") (pin "8") (pinfunction "VSS_8") (pintype "passive"))
      (node (ref "D9") (pin "3") (pinfunction "VSS_3") (pintype "passive"))
      (node (ref "D9") (pin "8") (pinfunction "VSS_8") (pintype "passive"))
      (node (ref "J4") (pin "1") (pinfunction "Shield_1") (pintype "passive"))
      (node (ref "J4") (pin "2") (pinfunction "Shield_2") (pintype "passive"))
      (node (ref "J4") (pin "3") (pinfunction "Shield_3") (pintype "passive"))
      (node (ref "J4") (pin "4") (pinfunction "Shield_4") (pintype "passive"))
      (node (ref "J4") (pin "A1") (pinfunction "GND_A1") (pintype "passive"))
      (node (ref "J4") (pin "A12") (pinfunction "GND_A12") (pintype "passive"))
      (node (ref "J4") (pin "B1") (pinfunction "GND_B1") (pintype "passive"))
      (node (ref "J4") (pin "B12") (pinfunction "GND_B12") (pintype "passive"))
      (node (ref "J5") (pin "1") (pinfunction "Shield_1") (pintype "passive"))
      (node (ref "J5") (pin "2") (pinfunction "Shield_2") (pintype "passive"))
      (node (ref "J5") (pin "3") (pinfunction "Shield_3") (pintype "passive"))
      (node (ref "J5") (pin "4") (pinfunction "Shield_4") (pintype "passive"))
      (node (ref "J5") (pin "A1") (pinfunction "GND_A1") (pintype "passive"))
      (node (ref "J5") (pin "A12") (pinfunction "GND_A12") (pintype "passive"))
      (node (ref "J5") (pin "B1") (pinfunction "GND_B1") (pintype "passive"))
      (node (ref "J5") (pin "B12") (pinfunction "GND_B12") (pintype "passive"))
      (node (ref "Q3") (pin "2") (pinfunction "S_2") (pintype "passive"))
      (node (ref "Q4") (pin "2") (pinfunction "S_2") (pintype "passive"))
      (node (ref "R106") (pin "2") (pinfunction "2_2") (pintype "passive"))
      (node (ref "R108") (pin "1") (pinfunction "1_1") (pintype "passive"))
      (node (ref "R118") (pin "2") (pinfunction "2_2") (pintype "passive"))
      (node (ref "R127") (pin "2") (pinfunction "2_2") (pintype "passive"))
      (node (ref "R133") (pin "2") (pinfunction "2_2") (pintype "passive"))
      (node (ref "R97") (pin "2") (pinfunction "2_2") (pintype "passive"))
      (node (ref "U10") (pin "1") (pinfunction "GND_1") (pintype "passive"))
      (node (ref "U10") (pin "9") (pinfunction "EP_9") (pintype "passive"))
      (node (ref "U11") (pin "2") (pinfunction "GND_2") (pintype "passive"))
      (node (ref "U15") (pin "4") (pinfunction "GND_4") (pintype "passive"))
      (node (ref "U16") (pin "12") (pinfunction "GND_12") (pintype "passive"))
      (node (ref "U16") (pin "17") (pinfunction "EPAD_17") (pintype "passive"))
      (node (ref "U17") (pin "5") (pinfunction "GND_5") (pintype "passive"))
      (node (ref "U18") (pin "7") (pinfunction "GND_7") (pintype "passive"))
      (node (ref "U19") (pin "4") (pinfunction "GND_4") (pintype "passive"))
      (node (ref "U20") (pin "2") (pinfunction "GND_2") (pintype "passive"))
      (node (ref "U21") (pin "11") (pinfunction "EP_11") (pintype "passive"))
      (node (ref "U21") (pin "3") (pinfunction "GND_3") (pintype "passive"))
      (node (ref "U22") (pin "1") (pinfunction "GND_1") (pintype "passive"))
      (node (ref "U22") (pin "9") (pinfunction "EP_9") (pintype "passive"))
      (node (ref "U23") (pin "2") (pinfunction "GND_2") (pintype "passive"))
      (node (ref "U25") (pin "2") (pinfunction "GND_2") (pintype "passive"))
      (node (ref "U27") (pin "11") (pinfunction "EP_11") (pintype "passive"))
      (node (ref "U27") (pin "3") (pinfunction "GND_3") (pintype "passive"))
      (node (ref "U28") (pin "3") (pinfunction "GND_3") (pintype "passive"))
      (node (ref "U29") (pin "3") (pinfunction "GND_3") (pintype "passive"))
      (node (ref "U34") (pin "3") (pinfunction "GND_3") (pintype "passive"))
      (node (ref "U35") (pin "3") (pinfunction "GND_3") (pintype "passive"))
      (node (ref "U36") (pin "3") (pinfunction "GND_3") (pintype "passive"))
      (node (ref "U37") (pin "3") (pinfunction "GND_3") (pintype "passive"))
    )
    (net (code "64") (name "Net-(D14-PadA)") (class "Default")
      (node (ref "D14") (pin "A") (pinfunction "A_A") (pintype "passive"))
      (node (ref "R115") (pin "1") (pinfunction "1_1") (pintype "passive"))
    )
    (net (code "65") (name "Net-(D17-PadA)") (class "Default")
      (node (ref "D17") (pin "A") (pinfunction "A_A") (pintype "passive"))
      (node (ref "R77") (pin "1") (pinfunction "1_1") (pintype "passive"))
    )
    (net (code "66") (name "Net-(D19-PadA)") (class "Default")
      (node (ref "D19") (pin "A") (pinfunction "A_A") (pintype "passive"))
      (node (ref "R110") (pin "1") (pinfunction "1_1") (pintype "passive"))
    )
    (net (code "67") (name "Net-(D20-PadA)") (class "Default")
      (node (ref "D20") (pin "A") (pinfunction "A_A") (pintype "passive"))
      (node (ref "R123") (pin "1") (pinfunction "1_1") (pintype "passive"))
    )
    (net (code "68") (name "Net-(Q3-D)") (class "Default")
      (node (ref "D17") (pin "K") (pinfunction "K_K") (pintype "passive"))
      (node (ref "Q3") (pin "3") (pinfunction "D_3") (pintype "passive"))
    )
    (net (code "69") (name "Net-(Q4-D)") (class "Default")
      (node (ref "D19") (pin "K") (pinfunction "K_K") (pintype "passive"))
      (node (ref "Q4") (pin "3") (pinfunction "D_3") (pintype "passive"))
    )
    (net (code "70") (name "Net-(U16-IN1+)") (class "Default")
      (node (ref "R100") (pin "2") (pinfunction "2_2") (pintype "passive"))
      (node (ref "R106") (pin "1") (pinfunction "1_1") (pintype "passive"))
      (node (ref "U16") (pin "11") (pinfunction "IN4+_11") (pintype "passive"))
      (node (ref "U16") (pin "4") (pinfunction "IN1+_4") (pintype "passive"))
      (node (ref "U16") (pin "6") (pinfunction "IN2+_6") (pintype "passive"))
      (node (ref "U16") (pin "8") (pinfunction "IN3+_8") (pintype "passive"))
    )
    (net (code "71") (name "Net-(U16-IN2-)") (class "Default")
      (node (ref "R107") (pin "2") (pinfunction "2_2") (pintype "passive"))
      (node (ref "R108") (pin "2") (pinfunction "2_2") (pintype "passive"))
      (node (ref "U16") (pin "5") (pinfunction "IN2-_5") (pintype "passive"))
      (node (ref "U16") (pin "7") (pinfunction "IN3-_7") (pintype "passive"))
    )
    (net (code "72") (name "Net-(U16-OUT2)") (class "Default")
      (node (ref "R102") (pin "1") (pinfunction "1_1") (pintype "passive"))
      (node (ref "U16") (pin "15") (pinfunction "OUT2_15") (pintype "passive"))
    )
    (net (code "73") (name "Net-(U16-OUT3)") (class "Default")
      (node (ref "R105") (pin "1") (pinfunction "1_1") (pintype "passive"))
      (node (ref "U16") (pin "14") (pinfunction "OUT3_14") (pintype "passive"))
    )
    (net (code "74") (name "Net-(U21-Ilim)") (class "Default")
      (node (ref "R152") (pin "2") (pinfunction "2_2") (pintype "passive"))
      (node (ref "U21") (pin "8") (pinfunction "Ilim_8") (pintype "passive"))
    )
    (net (code "75") (name "Net-(U21-VC_SEL)") (class "Default")
      (node (ref "R127") (pin "1") (pinfunction "1_1") (pintype "passive"))
      (node (ref "U21") (pin "5") (pinfunction "VC_SEL_5") (pintype "passive"))
    )
    (net (code "76") (name "Net-(U27-Ilim)") (class "Default")
      (node (ref "R151") (pin "2") (pinfunction "2_2") (pintype "passive"))
      (node (ref "U27") (pin "8") (pinfunction "Ilim_8") (pintype "passive"))
    )
    (net (code "77") (name "Net-(U27-VC_SEL)") (class "Default")
      (node (ref "R133") (pin "1") (pinfunction "1_1") (pintype "passive"))
      (node (ref "U27") (pin "5") (pinfunction "VC_SEL_5") (pintype "passive"))
    )
    (net (code "78") (name "Net-(U34-Y)") (class "Default")
      (node (ref "R164") (pin "1") (pinfunction "1_1") (pintype "passive"))
      (node (ref "U34") (pin "4") (pinfunction "Y_4") (pintype "passive"))
    )
    (net (code "79") (name "Net-(U35-Y)") (class "Default")
      (node (ref "R174") (pin "1") (pinfunction "1_1") (pintype "passive"))
      (node (ref "U35") (pin "4") (pinfunction "Y_4") (pintype "passive"))
    )
    (net (code "80") (name "unconnected-(U10-NC-Pad4)") (class "Default")
      (node (ref "U10") (pin "4") (pinfunction "NC_4") (pintype "passive+no_connect"))
    )
    (net (code "81") (name "unconnected-(U16-NC-Pad3)") (class "Default")
      (node (ref "U16") (pin "3") (pinfunction "NC_3") (pintype "passive+no_connect"))
    )
    (net (code "82") (name "unconnected-(U16-NC-Pad10)") (class "Default")
      (node (ref "U16") (pin "10") (pinfunction "NC_10") (pintype "passive+no_connect"))
    )
    (net (code "83") (name "unconnected-(U21-IMON-Pad4)") (class "Default")
      (node (ref "U21") (pin "4") (pinfunction "IMON_4") (pintype "passive+no_connect"))
    )
    (net (code "84") (name "unconnected-(U22-NC-Pad4)") (class "Default")
      (node (ref "U22") (pin "4") (pinfunction "NC_4") (pintype "passive+no_connect"))
    )
    (net (code "85") (name "unconnected-(U27-IMON-Pad4)") (class "Default")
      (node (ref "U27") (pin "4") (pinfunction "IMON_4") (pintype "passive+no_connect"))
    )
    (net (code "86") (name "unconnected-(U28-NC-Pad1)") (class "Default")
      (node (ref "U28") (pin "1") (pinfunction "NC_1") (pintype "passive+no_connect"))
    )
    (net (code "87") (name "unconnected-(U29-NC-Pad1)") (class "Default")
      (node (ref "U29") (pin "1") (pinfunction "NC_1") (pintype "passive+no_connect"))
    )
    (net (code "88") (name "unconnected-(U36-NC-Pad1)") (class "Default")
      (node (ref "U36") (pin "1") (pinfunction "NC_1") (pintype "passive+no_connect"))
    )
    (net (code "89") (name "unconnected-(U37-NC-Pad1)") (class "Default")
      (node (ref "U37") (pin "1") (pinfunction "NC_1") (pintype "passive+no_connect"))
    )
  )
)
